# Stromlaufplan_3D-Drucker-Dominik_und_Sam.net
KiCad netlist of a schematic drawn in EAGLE
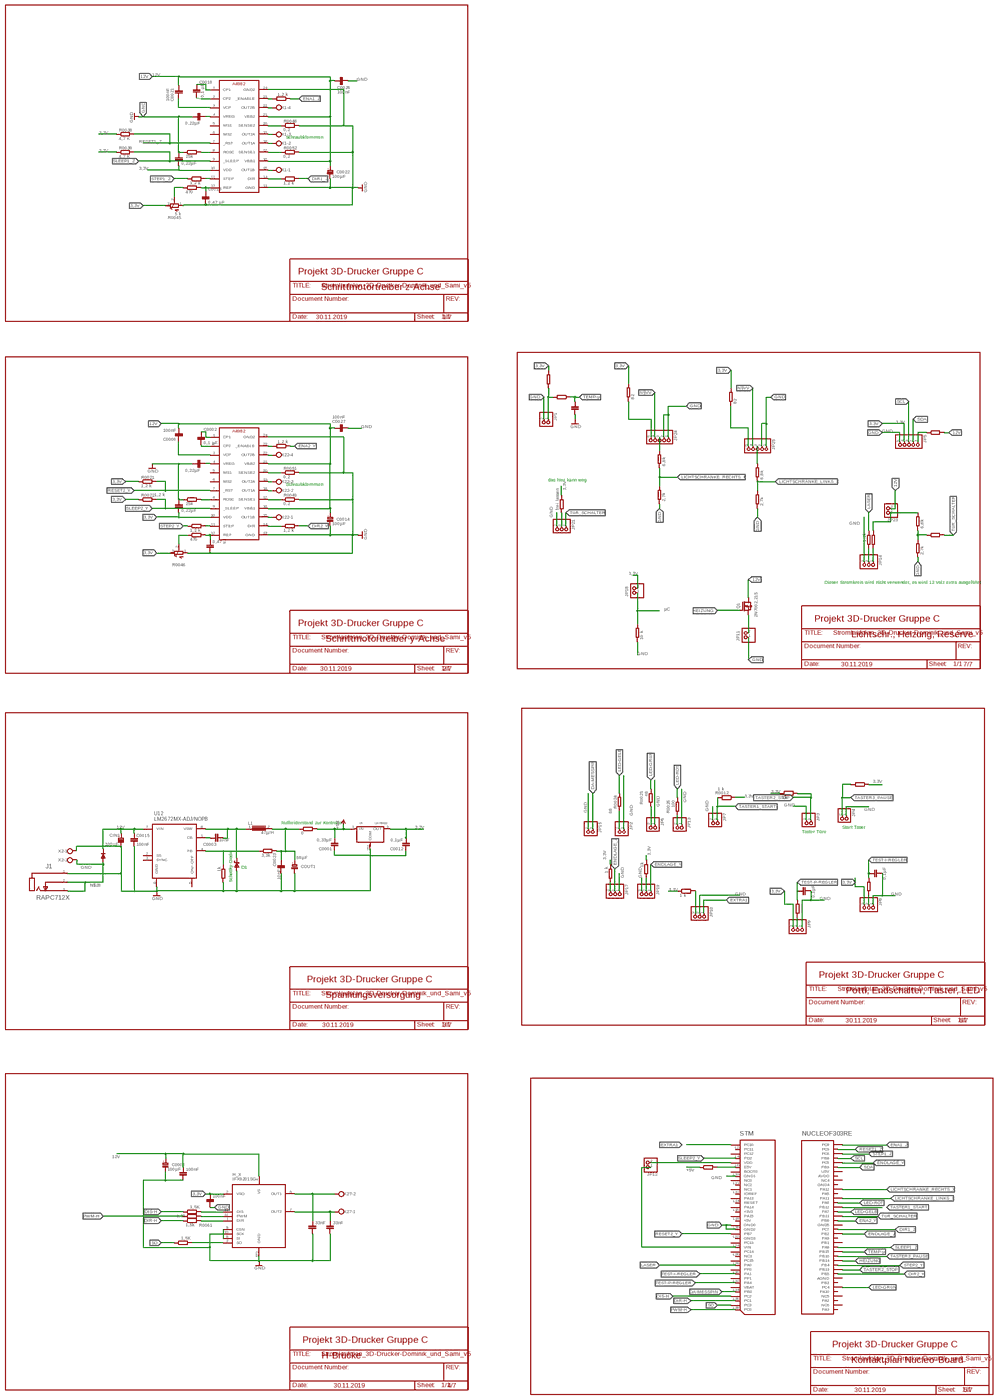
[diagram p0: schematic, sheet 1, overview]
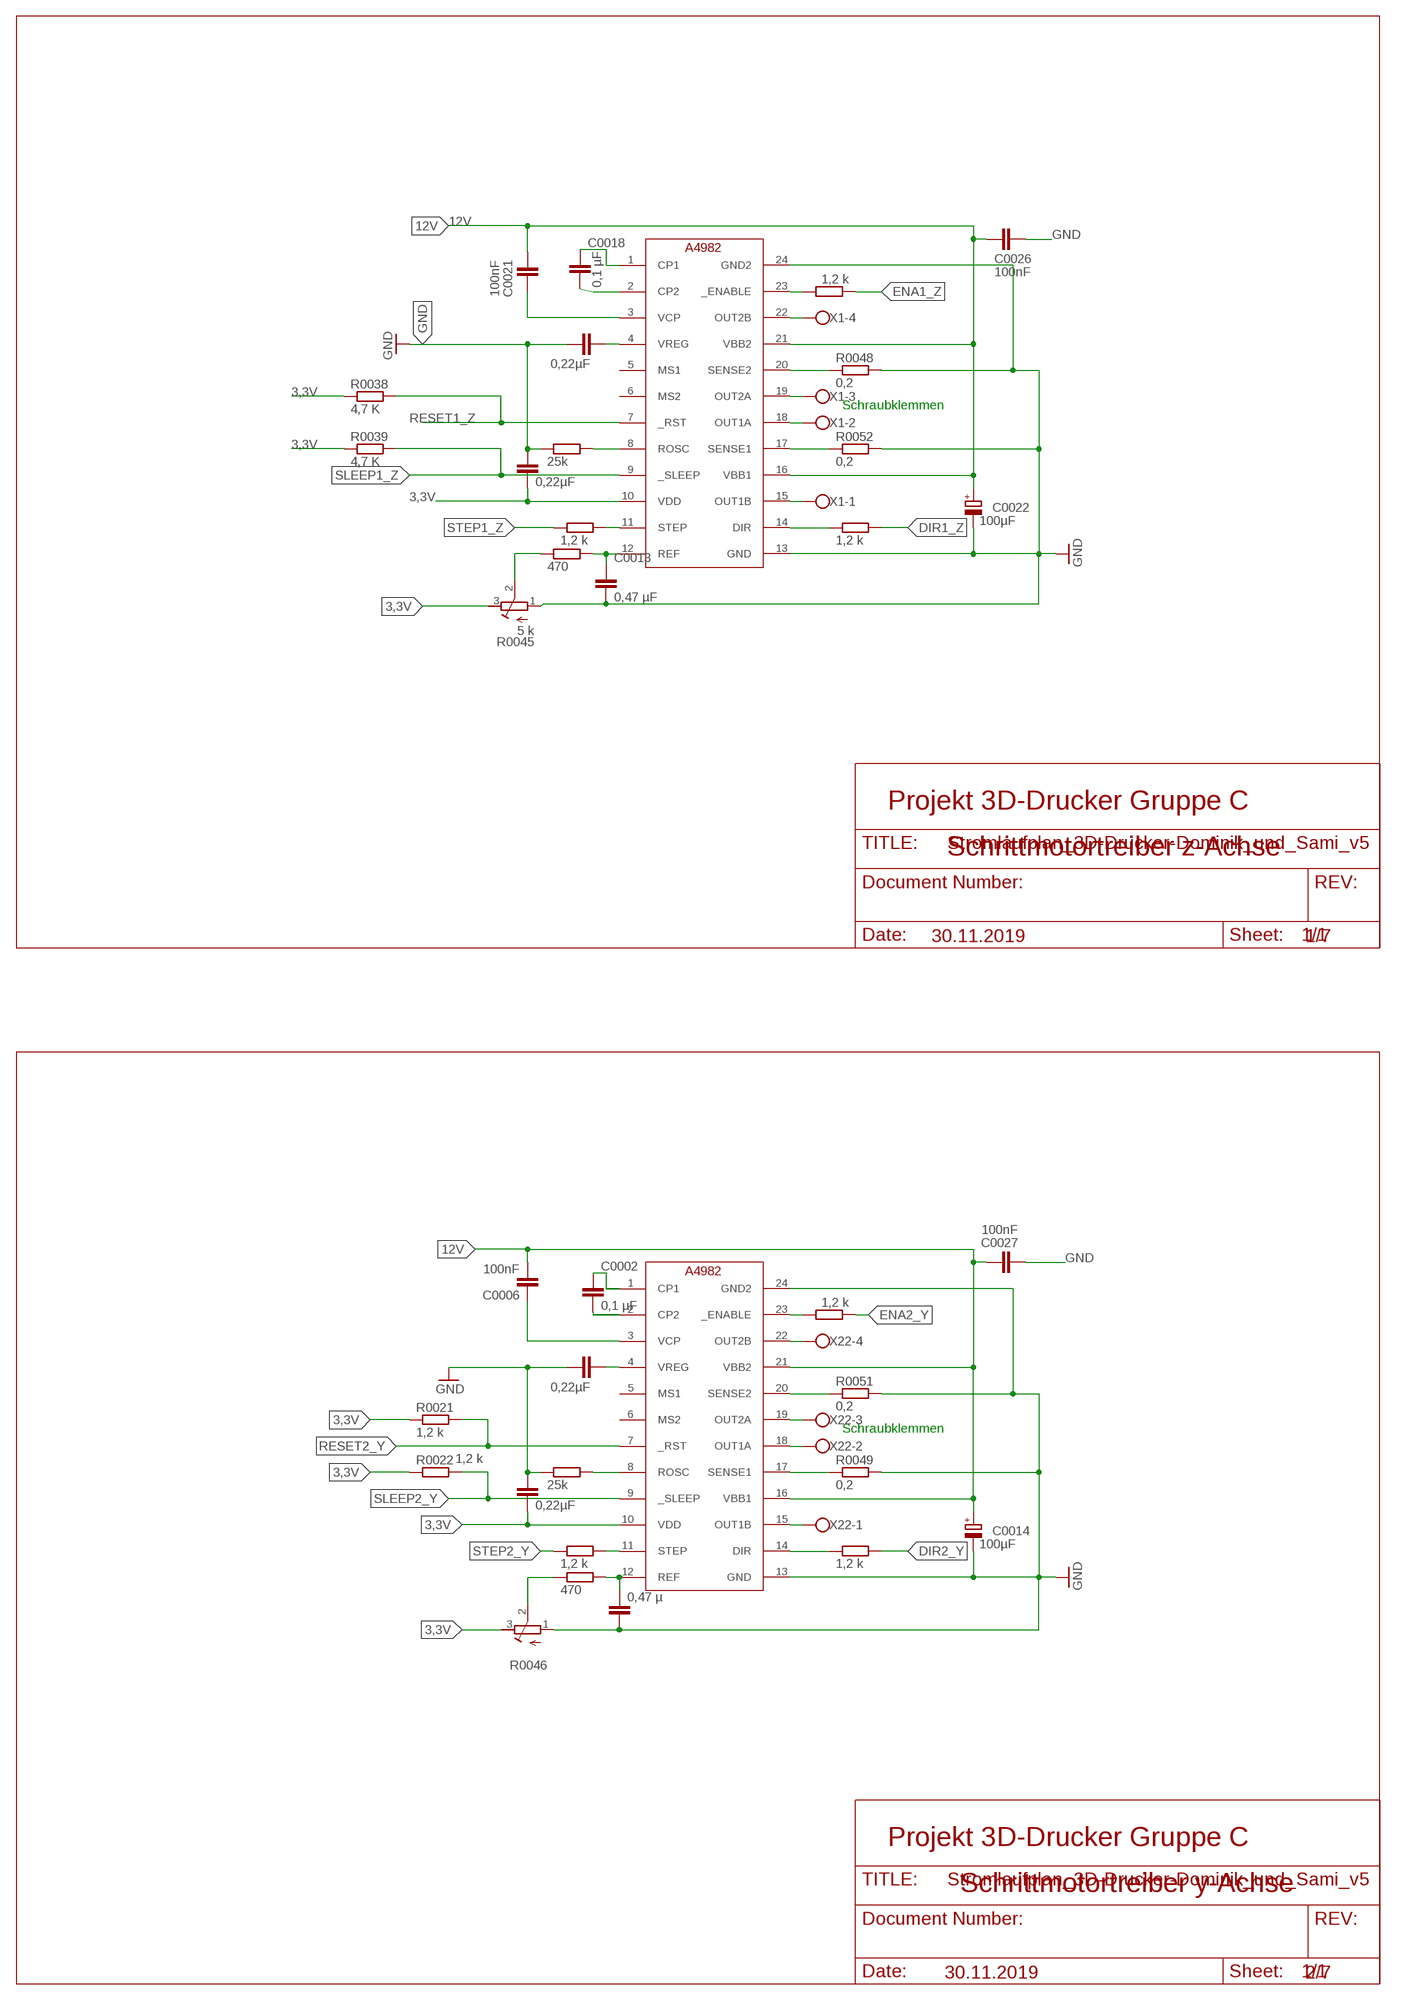
[diagram p1: schematic, sheet 1, part 1 of 4]
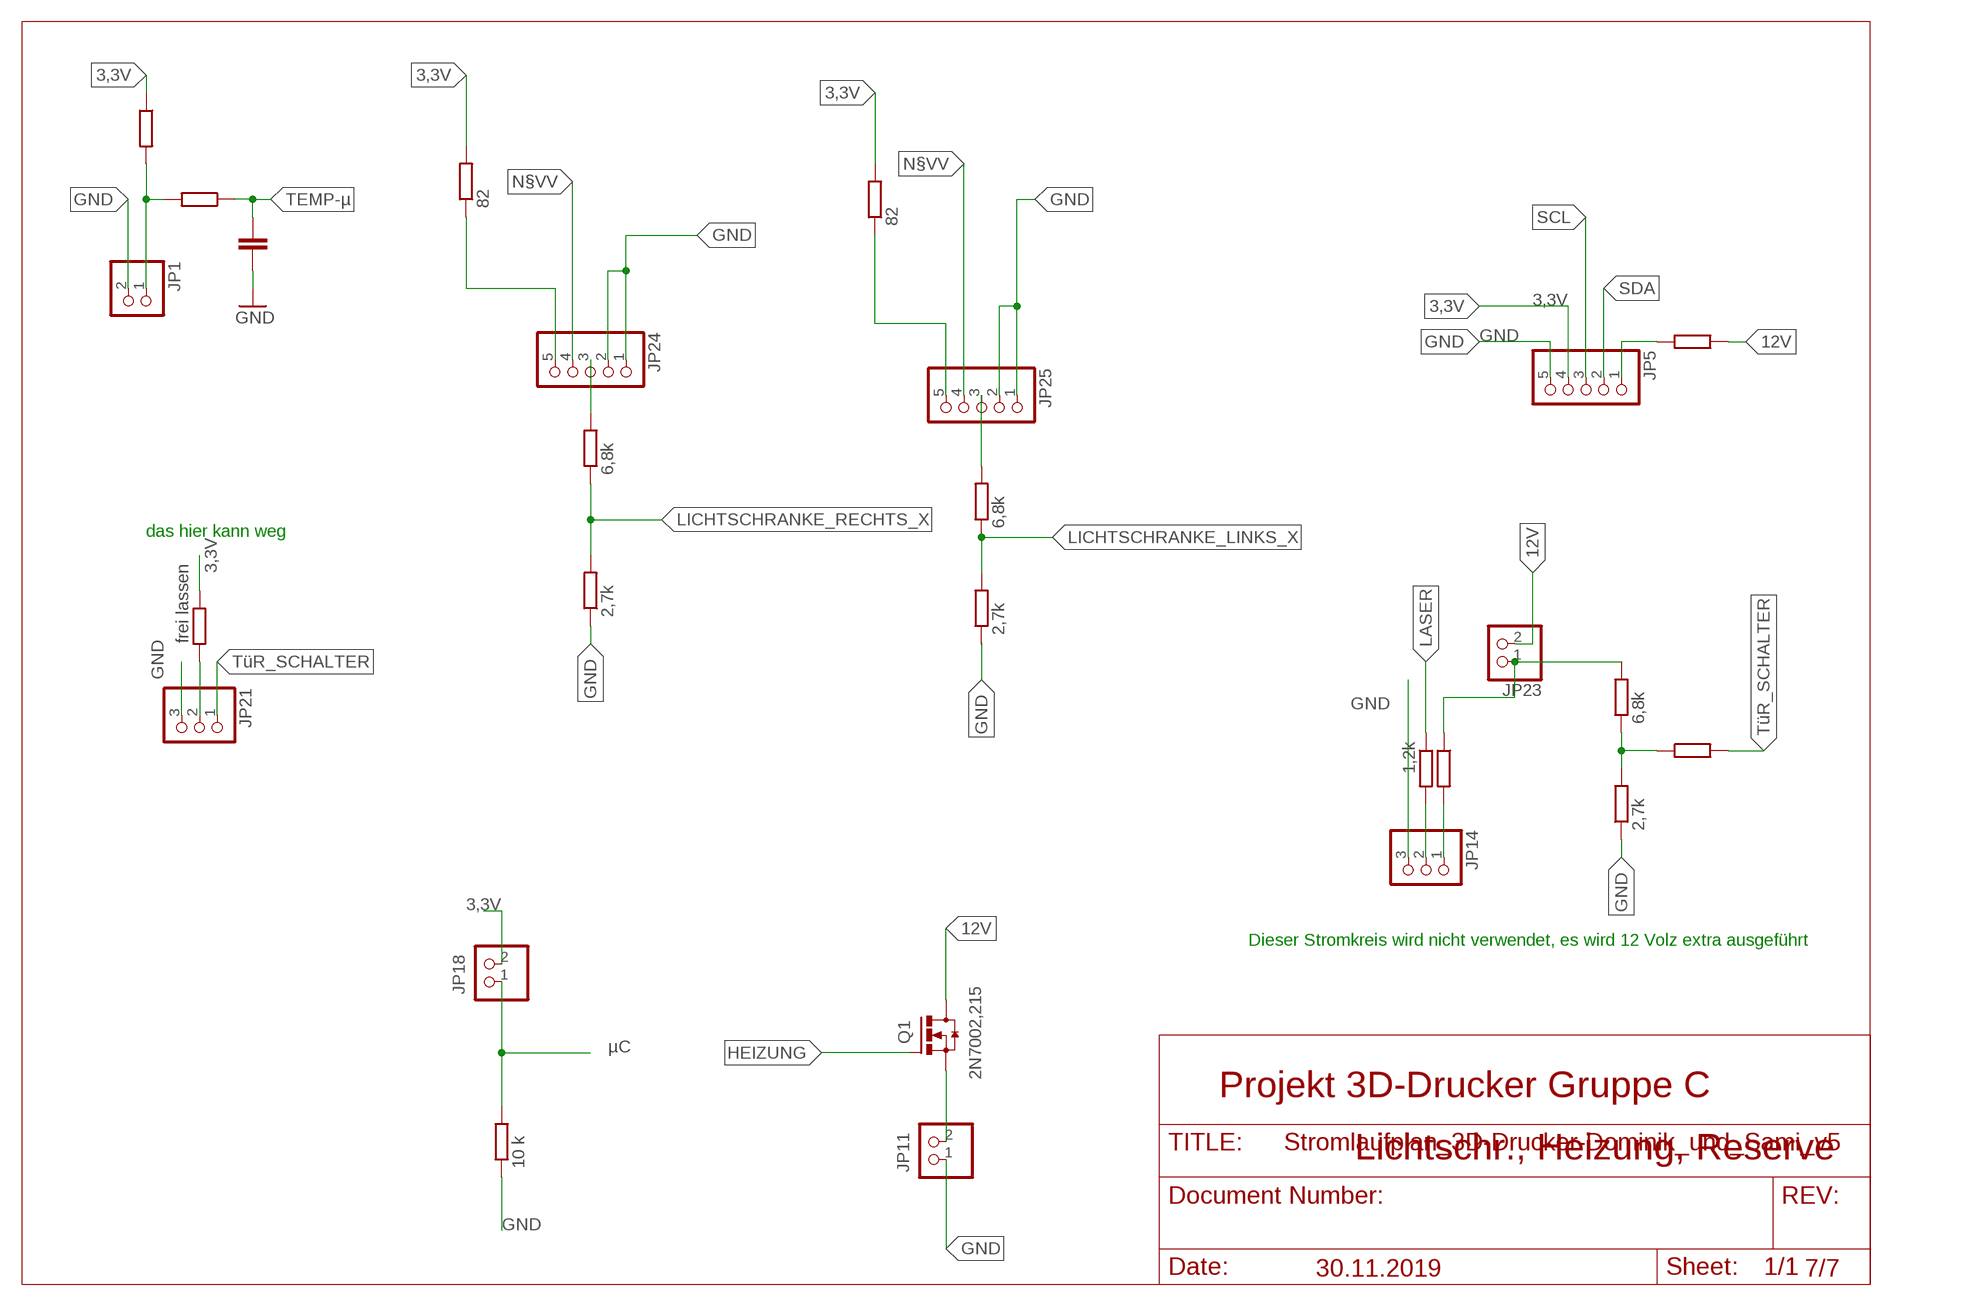
[diagram p2: schematic, sheet 1, part 2 of 4]
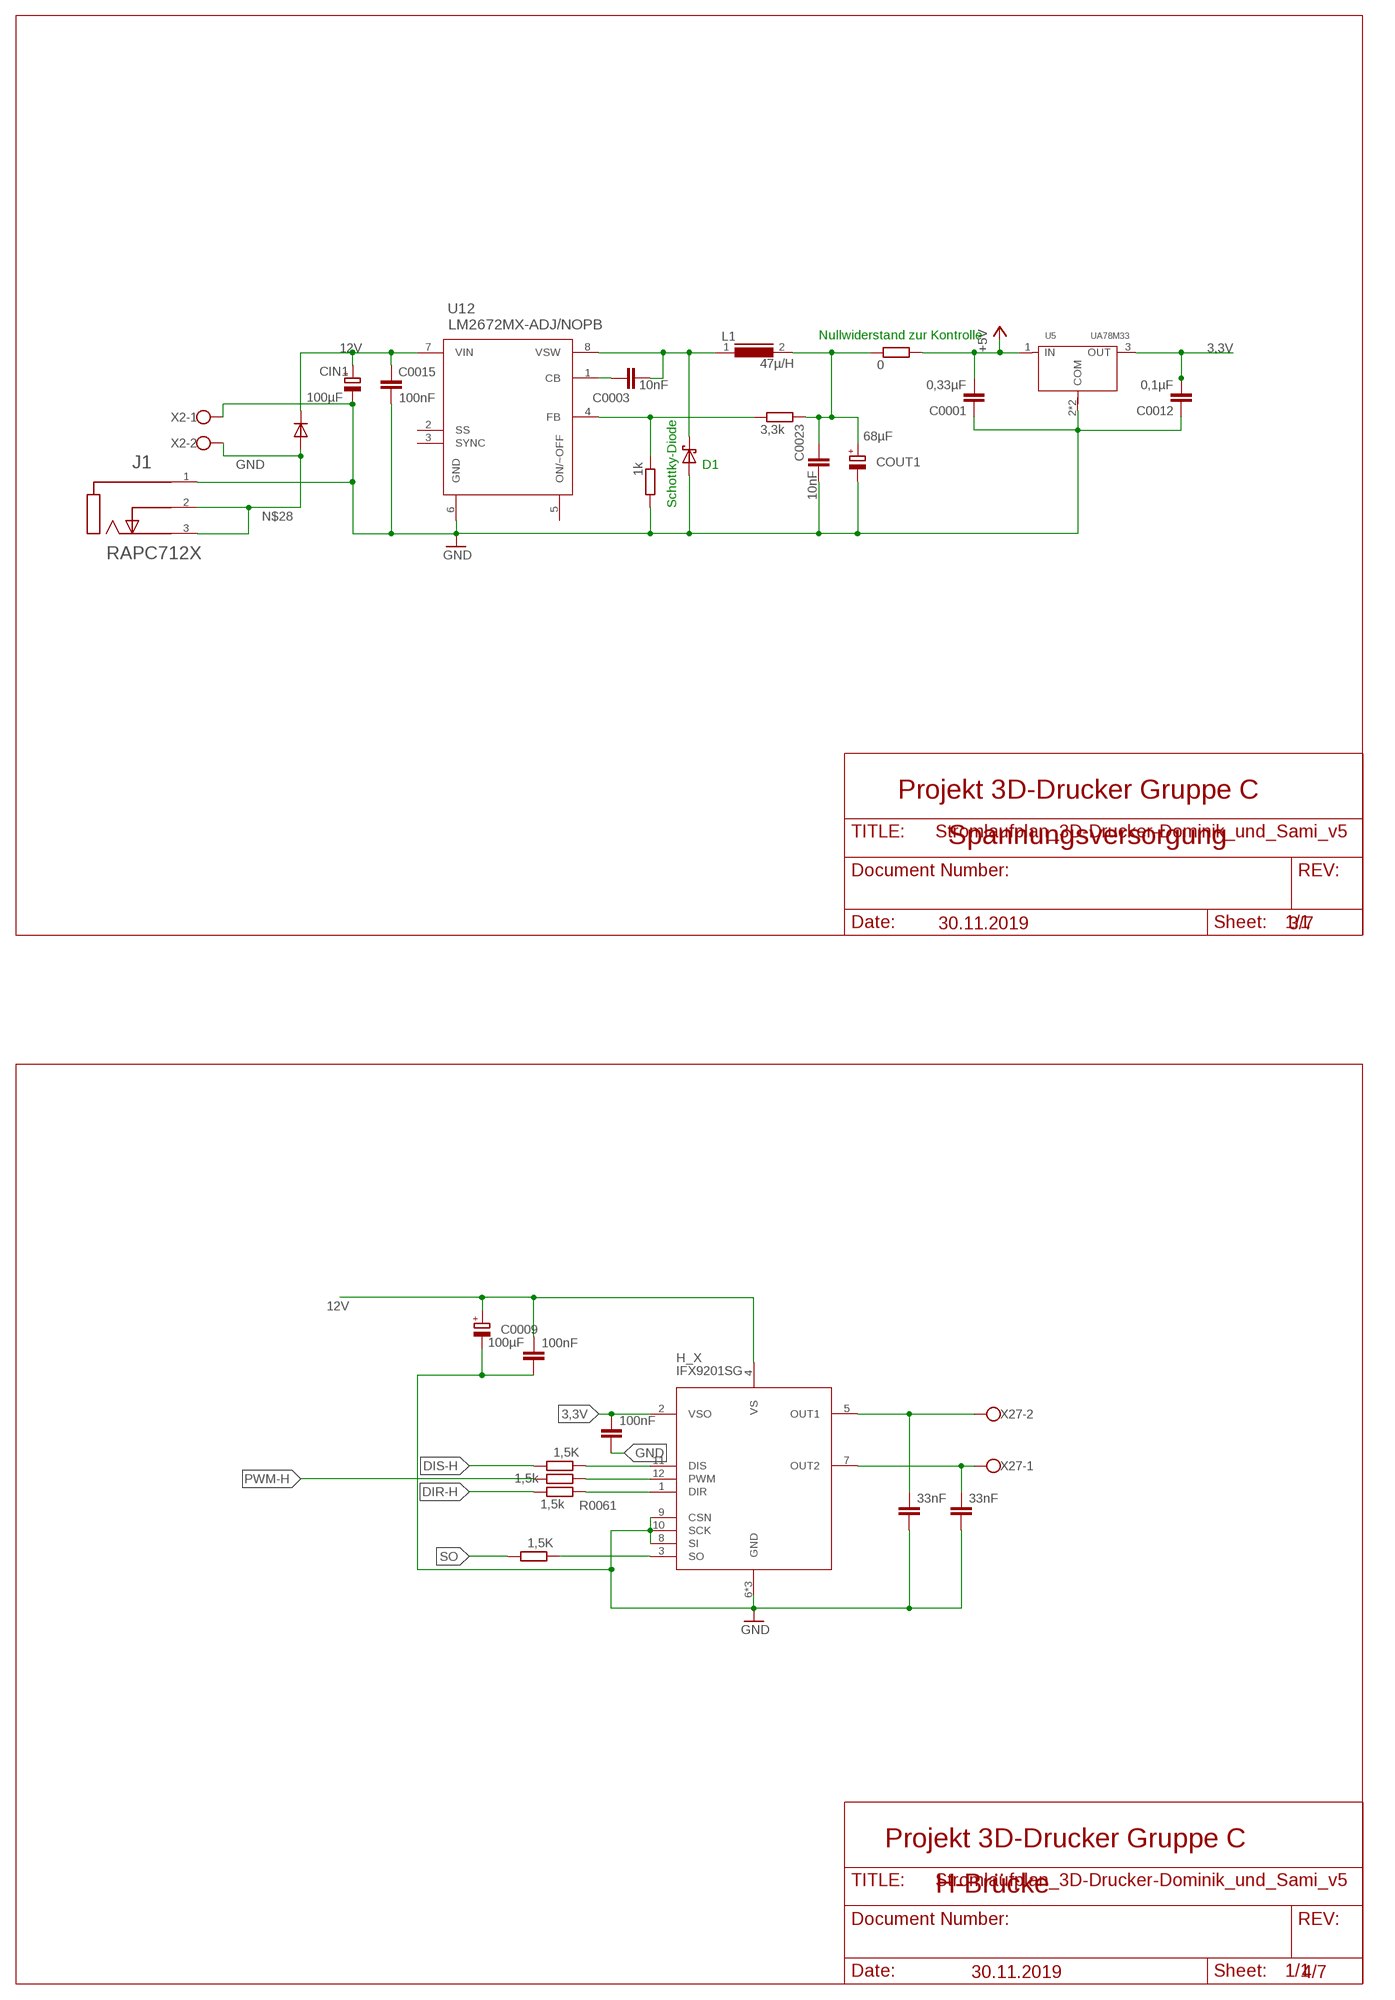
[diagram p3: schematic, sheet 1, part 3 of 4]
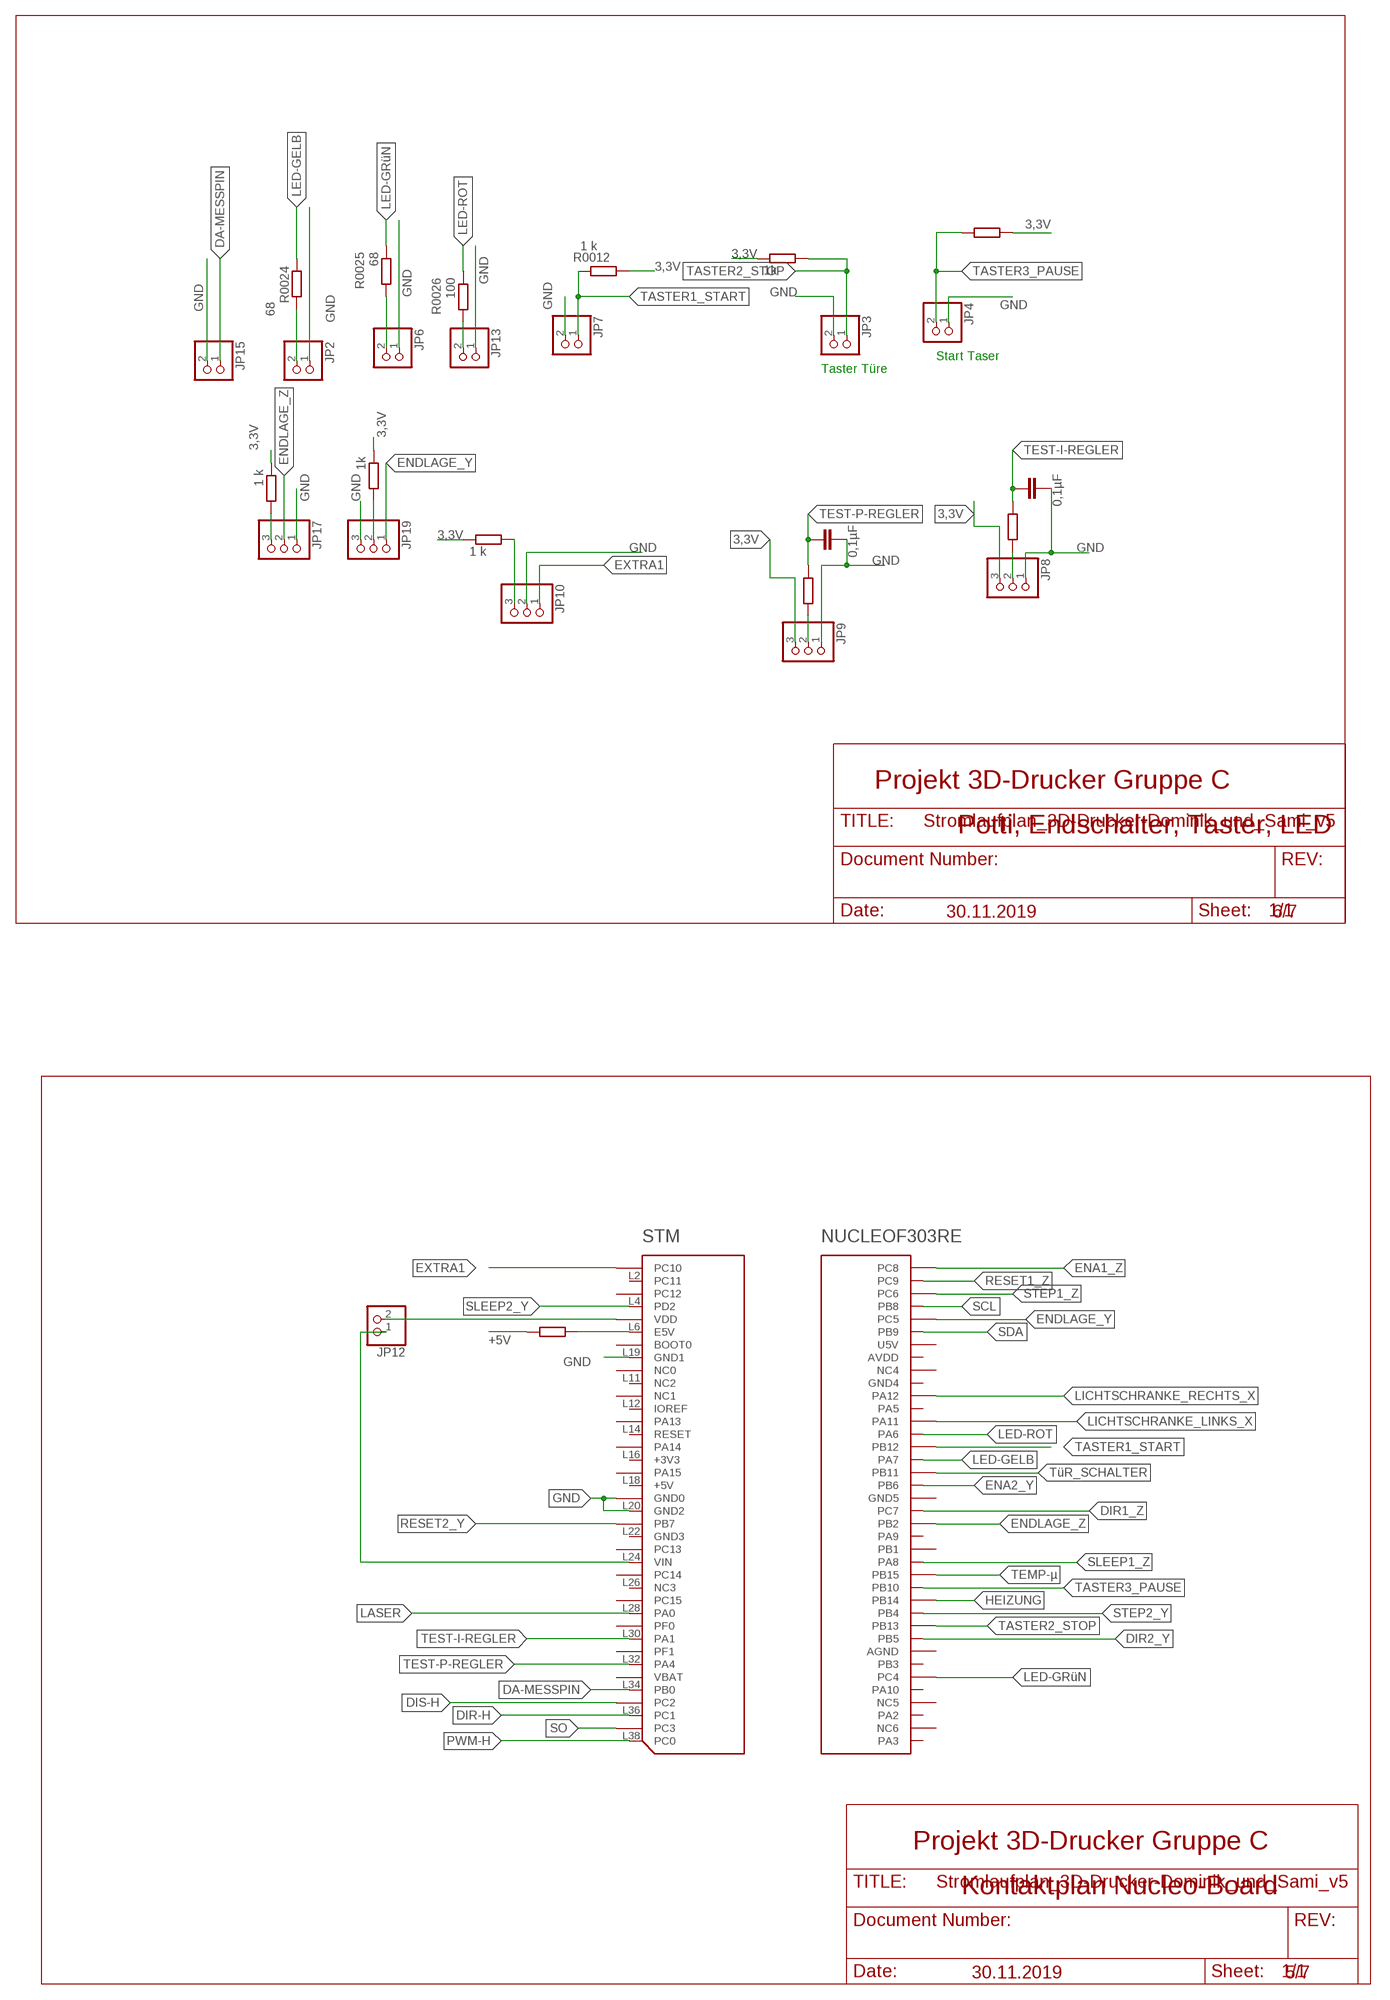
[diagram p4: schematic, sheet 1, part 4 of 4]

(export (version "E")
  (design (tool "Eeschema 10.0.6"))
  (components
    (comp (ref "A4982_Y")
      (value "A4982_STEPDRIVER")
      (footprint "eagle-import:TSSOP24")
      (libsource (lib "eagle-import") (part "A4982_STEPDRIVER"))
    )
    (comp (ref "A4982_Y1")
      (value "A4982_STEPDRIVER")
      (footprint "eagle-import:TSSOP24")
      (libsource (lib "eagle-import") (part "A4982_STEPDRIVER"))
    )
    (comp (ref "C0001")
      (value "0,33µF")
      (footprint "eagle-import:C0603")
      (libsource (lib "eagle-import") (part "C-EUC0603"))
    )
    (comp (ref "C0002")
      (value "0,1 µF")
      (footprint "eagle-import:C0603")
      (libsource (lib "eagle-import") (part "C-EUC0603"))
    )
    (comp (ref "C0003")
      (value "10nF")
      (footprint "eagle-import:C0603")
      (libsource (lib "eagle-import") (part "C-EUC0603"))
    )
    (comp (ref "C0004")
      (value "0,22µF")
      (footprint "eagle-import:C0603")
      (libsource (lib "eagle-import") (part "C-EUC0603"))
    )
    (comp (ref "C0005")
      (value "0,22µF")
      (footprint "eagle-import:C0603")
      (libsource (lib "eagle-import") (part "C-EUC0603"))
    )
    (comp (ref "C0006")
      (value "100nF")
      (footprint "eagle-import:C0603")
      (libsource (lib "eagle-import") (part "C-EUC0603"))
    )
    (comp (ref "C0007")
      (value "33nF")
      (footprint "eagle-import:C0805")
      (libsource (lib "eagle-import") (part "C-EUC0805"))
    )
    (comp (ref "C0008")
      (value "33nF")
      (footprint "eagle-import:C0805")
      (libsource (lib "eagle-import") (part "C-EUC0805"))
    )
    (comp (ref "C0009")
      (value "100µF")
      (footprint "eagle-import:UD-8X10_NICHICON")
      (libsource (lib "eagle-import") (part "CPOL-EUUD-8X10"))
    )
    (comp (ref "C0010")
      (value "0,47 µ")
      (footprint "eagle-import:C0805")
      (libsource (lib "eagle-import") (part "C-EUC0805"))
    )
    (comp (ref "C0011")
      (value "C-EUC0805")
      (footprint "eagle-import:C0805")
      (libsource (lib "eagle-import") (part "C-EUC0805"))
    )
    (comp (ref "C0012")
      (value "0,1µF")
      (footprint "eagle-import:C0603")
      (libsource (lib "eagle-import") (part "C-EUC0603"))
    )
    (comp (ref "C0013")
      (value "0,47 µF")
      (footprint "eagle-import:C0603")
      (libsource (lib "eagle-import") (part "C-EUC0603"))
    )
    (comp (ref "C0014")
      (value "100µF")
      (footprint "eagle-import:UD-8X10_NICHICON")
      (libsource (lib "eagle-import") (part "CPOL-EUUD-8X10"))
    )
    (comp (ref "C0015")
      (value "100nF")
      (footprint "eagle-import:C0603")
      (libsource (lib "eagle-import") (part "C-EUC0603"))
    )
    (comp (ref "C0016")
      (value "100nF")
      (footprint "eagle-import:C0805")
      (libsource (lib "eagle-import") (part "C-EUC0805"))
    )
    (comp (ref "C0018")
      (value "0,1 µF")
      (footprint "eagle-import:C0603")
      (libsource (lib "eagle-import") (part "C-EUC0603"))
    )
    (comp (ref "C0019")
      (value "0,22µF")
      (footprint "eagle-import:C0603")
      (libsource (lib "eagle-import") (part "C-EUC0603"))
    )
    (comp (ref "C0020")
      (value "0,22µF")
      (footprint "eagle-import:C0603")
      (libsource (lib "eagle-import") (part "C-EUC0603"))
    )
    (comp (ref "C0021")
      (value "100nF")
      (footprint "eagle-import:C0603")
      (libsource (lib "eagle-import") (part "C-EUC0603"))
    )
    (comp (ref "C0022")
      (value "100µF")
      (footprint "eagle-import:UD-8X10_NICHICON")
      (libsource (lib "eagle-import") (part "CPOL-EUUD-8X10"))
    )
    (comp (ref "C0023")
      (value "10nF")
      (footprint "eagle-import:C0603")
      (libsource (lib "eagle-import") (part "C-EUC0603"))
    )
    (comp (ref "C0024")
      (value "0,1µF")
      (footprint "eagle-import:C0603")
      (libsource (lib "eagle-import") (part "C-EUC0603"))
    )
    (comp (ref "C0025")
      (value "0,1µF")
      (footprint "eagle-import:C0603")
      (libsource (lib "eagle-import") (part "C-EUC0603"))
    )
    (comp (ref "C0026")
      (value "100nF")
      (footprint "eagle-import:C0603")
      (libsource (lib "eagle-import") (part "C-EUC0603"))
    )
    (comp (ref "C0027")
      (value "100nF")
      (footprint "eagle-import:C0603")
      (libsource (lib "eagle-import") (part "C-EUC0603"))
    )
    (comp (ref "C0041")
      (value "100nF")
      (footprint "eagle-import:C0805")
      (libsource (lib "eagle-import") (part "C-EUC0805"))
    )
    (comp (ref "CIN1")
      (value "100µF")
      (footprint "eagle-import:140CLH-1010")
      (libsource (lib "eagle-import") (part "CPOL-EU140CLH-1010"))
    )
    (comp (ref "COUT1")
      (value "68µF")
      (footprint "eagle-import:140CLH-1010")
      (libsource (lib "eagle-import") (part "CPOL-EU140CLH-1010"))
    )
    (comp (ref "D1")
      (value "1N5819HW-7-F")
      (footprint "eagle-import:SOD-123_MINI-SMA")
      (libsource (lib "eagle-import") (part "1N5819HW-7-F"))
    )
    (comp (ref "D12")
      (value "MURS360BT3G")
      (footprint "eagle-import:SMB")
      (libsource (lib "eagle-import") (part "MURS360BT3G"))
    )
    (comp (ref "H_X")
      (value "IFX9201SG")
      (footprint "eagle-import:BSOP-12")
      (libsource (lib "eagle-import") (part "IFX9201SG"))
    )
    (comp (ref "J1")
      (value "RAPC712X")
      (footprint "eagle-import:SWC_RAPC712X")
      (fields (field (name "MF") "Switchcraft"))
      (libsource (lib "eagle-import") (part "RAPC712X"))
    )
    (comp (ref "JP1")
      (value "PINHD-1X2")
      (footprint "eagle-import:1X02")
      (libsource (lib "eagle-import") (part "PINHD-1X2"))
    )
    (comp (ref "JP2")
      (value "PINHD-1X2")
      (footprint "eagle-import:1X02")
      (libsource (lib "eagle-import") (part "PINHD-1X2"))
    )
    (comp (ref "JP3")
      (value "PINHD-1X2")
      (footprint "eagle-import:1X02")
      (libsource (lib "eagle-import") (part "PINHD-1X2"))
    )
    (comp (ref "JP4")
      (value "PINHD-1X2")
      (footprint "eagle-import:1X02")
      (libsource (lib "eagle-import") (part "PINHD-1X2"))
    )
    (comp (ref "JP5")
      (value "PINHD-1X5")
      (footprint "eagle-import:1X05")
      (libsource (lib "eagle-import") (part "PINHD-1X5"))
    )
    (comp (ref "JP6")
      (value "PINHD-1X2")
      (footprint "eagle-import:1X02")
      (libsource (lib "eagle-import") (part "PINHD-1X2"))
    )
    (comp (ref "JP7")
      (value "PINHD-1X2")
      (footprint "eagle-import:1X02")
      (libsource (lib "eagle-import") (part "PINHD-1X2"))
    )
    (comp (ref "JP8")
      (value "PINHD-1X3")
      (footprint "eagle-import:1X03")
      (libsource (lib "eagle-import") (part "PINHD-1X3"))
    )
    (comp (ref "JP9")
      (value "PINHD-1X3")
      (footprint "eagle-import:1X03")
      (libsource (lib "eagle-import") (part "PINHD-1X3"))
    )
    (comp (ref "JP10")
      (value "PINHD-1X3")
      (footprint "eagle-import:1X03")
      (libsource (lib "eagle-import") (part "PINHD-1X3"))
    )
    (comp (ref "JP11")
      (value "PINHD-1X2")
      (footprint "eagle-import:1X02")
      (libsource (lib "eagle-import") (part "PINHD-1X2"))
    )
    (comp (ref "JP12")
      (value "PINHD-1X2")
      (footprint "eagle-import:1X02")
      (libsource (lib "eagle-import") (part "PINHD-1X2"))
    )
    (comp (ref "JP13")
      (value "PINHD-1X2")
      (footprint "eagle-import:1X02")
      (libsource (lib "eagle-import") (part "PINHD-1X2"))
    )
    (comp (ref "JP14")
      (value "PINHD-1X3")
      (footprint "eagle-import:1X03")
      (libsource (lib "eagle-import") (part "PINHD-1X3"))
    )
    (comp (ref "JP15")
      (value "PINHD-1X2")
      (footprint "eagle-import:1X02")
      (libsource (lib "eagle-import") (part "PINHD-1X2"))
    )
    (comp (ref "JP17")
      (value "PINHD-1X3")
      (footprint "eagle-import:1X03")
      (libsource (lib "eagle-import") (part "PINHD-1X3"))
    )
    (comp (ref "JP18")
      (value "PINHD-1X2")
      (footprint "eagle-import:1X02")
      (libsource (lib "eagle-import") (part "PINHD-1X2"))
    )
    (comp (ref "JP19")
      (value "PINHD-1X3")
      (footprint "eagle-import:1X03")
      (libsource (lib "eagle-import") (part "PINHD-1X3"))
    )
    (comp (ref "JP21")
      (value "PINHD-1X3")
      (footprint "eagle-import:1X03")
      (libsource (lib "eagle-import") (part "PINHD-1X3"))
    )
    (comp (ref "JP23")
      (value "PINHD-1X2")
      (footprint "eagle-import:1X02")
      (libsource (lib "eagle-import") (part "PINHD-1X2"))
    )
    (comp (ref "JP24")
      (value "PINHD-1X5")
      (footprint "eagle-import:1X05")
      (libsource (lib "eagle-import") (part "PINHD-1X5"))
    )
    (comp (ref "JP25")
      (value "PINHD-1X5")
      (footprint "eagle-import:1X05")
      (libsource (lib "eagle-import") (part "PINHD-1X5"))
    )
    (comp (ref "L1")
      (value "47µ/H")
      (footprint "eagle-import:INDUCTOR")
      (libsource (lib "eagle-import") (part "SRR1240-680M"))
    )
    (comp (ref "Q1")
      (value "2N7002,215")
      (footprint "eagle-import:SOT23-3")
      (fields
        (field (name "DIGIKEY_PART_NUMBER") "1727-2764-1-ND")
        (field (name "MANUFACTURER") "Nexperia USA Inc.")
        (field (name "CREATED_BY") "PCBLayout.com")
      )
      (libsource (lib "eagle-import") (part "2N7002,215"))
    )
    (comp (ref "R0001")
      (value "1,5K")
      (footprint "eagle-import:R0603")
      (libsource (lib "eagle-import") (part "R-EU_R0603"))
    )
    (comp (ref "R0002")
      (value "6,8k")
      (footprint "eagle-import:R0603")
      (libsource (lib "eagle-import") (part "R-EU_R0603"))
    )
    (comp (ref "R0003")
      (value "1k")
      (footprint "eagle-import:R0603")
      (libsource (lib "eagle-import") (part "R-EU_R0603"))
    )
    (comp (ref "R0004")
      (value "2,7k")
      (footprint "eagle-import:R0603")
      (libsource (lib "eagle-import") (part "R-EU_R0603"))
    )
    (comp (ref "R0005")
      (value "6,8k")
      (footprint "eagle-import:R0603")
      (libsource (lib "eagle-import") (part "R-EU_R0603"))
    )
    (comp (ref "R0006")
      (value "25k")
      (footprint "eagle-import:R0603")
      (libsource (lib "eagle-import") (part "R-EU_R0603"))
    )
    (comp (ref "R0007")
      (value "10 k")
      (footprint "eagle-import:R0603")
      (libsource (lib "eagle-import") (part "R-EU_R0603"))
    )
    (comp (ref "R0008")
      (value "R-EU_R0603")
      (footprint "eagle-import:R0603")
      (libsource (lib "eagle-import") (part "R-EU_R0603"))
    )
    (comp (ref "R0009")
      (value "1,2 k")
      (footprint "eagle-import:R0603")
      (libsource (lib "eagle-import") (part "R-EU_R0603"))
    )
    (comp (ref "R0010")
      (value "1,2 k")
      (footprint "eagle-import:R0603")
      (libsource (lib "eagle-import") (part "R-EU_R0603"))
    )
    (comp (ref "R0011")
      (value "1,2 k")
      (footprint "eagle-import:R0603")
      (libsource (lib "eagle-import") (part "R-EU_R0603"))
    )
    (comp (ref "R0012")
      (value "1 k")
      (footprint "eagle-import:R0603")
      (libsource (lib "eagle-import") (part "R-EU_R0603"))
    )
    (comp (ref "R0013")
      (value "1k")
      (footprint "eagle-import:R0603")
      (libsource (lib "eagle-import") (part "R-EU_R0603"))
    )
    (comp (ref "R0014")
      (value "R-EU_R0603")
      (footprint "eagle-import:R0603")
      (libsource (lib "eagle-import") (part "R-EU_R0603"))
    )
    (comp (ref "R0015")
      (value "1 k")
      (footprint "eagle-import:R0603")
      (libsource (lib "eagle-import") (part "R-EU_R0603"))
    )
    (comp (ref "R0016")
      (value "R-EU_R0603")
      (footprint "eagle-import:R0603")
      (libsource (lib "eagle-import") (part "R-EU_R0603"))
    )
    (comp (ref "R0017")
      (value "R-EU_R0603")
      (footprint "eagle-import:R0603")
      (libsource (lib "eagle-import") (part "R-EU_R0603"))
    )
    (comp (ref "R0018")
      (value "frei lassen")
      (footprint "eagle-import:R0603")
      (libsource (lib "eagle-import") (part "R-EU_R0603"))
    )
    (comp (ref "R0019")
      (value "25k")
      (footprint "eagle-import:R0603")
      (libsource (lib "eagle-import") (part "R-EU_R0603"))
    )
    (comp (ref "R0020")
      (value "R-EU_R0603")
      (footprint "eagle-import:R0603")
      (libsource (lib "eagle-import") (part "R-EU_R0603"))
    )
    (comp (ref "R0021")
      (value "1,2 k")
      (footprint "eagle-import:R0603")
      (libsource (lib "eagle-import") (part "R-EU_R0603"))
    )
    (comp (ref "R0022")
      (value "1,2 k")
      (footprint "eagle-import:R0603")
      (libsource (lib "eagle-import") (part "R-EU_R0603"))
    )
    (comp (ref "R0023")
      (value "470")
      (footprint "eagle-import:R0603")
      (libsource (lib "eagle-import") (part "R-EU_R0603"))
    )
    (comp (ref "R0024")
      (value "68")
      (footprint "eagle-import:R0603")
      (libsource (lib "eagle-import") (part "R-EU_R0603"))
    )
    (comp (ref "R0025")
      (value "68")
      (footprint "eagle-import:R0603")
      (libsource (lib "eagle-import") (part "R-EU_R0603"))
    )
    (comp (ref "R0026")
      (value "100")
      (footprint "eagle-import:R0603")
      (libsource (lib "eagle-import") (part "R-EU_R0603"))
    )
    (comp (ref "R0027")
      (value "R-EU_R0603")
      (footprint "eagle-import:R0603")
      (libsource (lib "eagle-import") (part "R-EU_R0603"))
    )
    (comp (ref "R0028")
      (value "2,7k")
      (footprint "eagle-import:R0603")
      (libsource (lib "eagle-import") (part "R-EU_R0603"))
    )
    (comp (ref "R0029")
      (value "82")
      (footprint "eagle-import:R0603")
      (libsource (lib "eagle-import") (part "R-EU_R0603"))
    )
    (comp (ref "R0030")
      (value "R-EU_R0603")
      (footprint "eagle-import:R0603")
      (libsource (lib "eagle-import") (part "R-EU_R0603"))
    )
    (comp (ref "R0031")
      (value "R-EU_R0603")
      (footprint "eagle-import:R0603")
      (libsource (lib "eagle-import") (part "R-EU_R0603"))
    )
    (comp (ref "R0032")
      (value "82")
      (footprint "eagle-import:R0603")
      (libsource (lib "eagle-import") (part "R-EU_R0603"))
    )
    (comp (ref "R0033")
      (value "1 k")
      (footprint "eagle-import:R0603")
      (libsource (lib "eagle-import") (part "R-EU_R0603"))
    )
    (comp (ref "R0034")
      (value "1,2 k")
      (footprint "eagle-import:R0603")
      (libsource (lib "eagle-import") (part "R-EU_R0603"))
    )
    (comp (ref "R0035")
      (value "1,2 k")
      (footprint "eagle-import:R0603")
      (libsource (lib "eagle-import") (part "R-EU_R0603"))
    )
    (comp (ref "R0036")
      (value "1,2 k")
      (footprint "eagle-import:R0603")
      (libsource (lib "eagle-import") (part "R-EU_R0603"))
    )
    (comp (ref "R0037")
      (value "470")
      (footprint "eagle-import:R0603")
      (libsource (lib "eagle-import") (part "R-EU_R0603"))
    )
    (comp (ref "R0038")
      (value "4,7 K")
      (footprint "eagle-import:R0603")
      (libsource (lib "eagle-import") (part "R-EU_R0603"))
    )
    (comp (ref "R0039")
      (value "4,7 K")
      (footprint "eagle-import:R0603")
      (libsource (lib "eagle-import") (part "R-EU_R0603"))
    )
    (comp (ref "R0042")
      (value "1,2k")
      (footprint "eagle-import:R0603")
      (libsource (lib "eagle-import") (part "R-EU_R0603"))
    )
    (comp (ref "R0043")
      (value "6,8k")
      (footprint "eagle-import:R0603")
      (libsource (lib "eagle-import") (part "R-EU_R0603"))
    )
    (comp (ref "R0044")
      (value "2,7k")
      (footprint "eagle-import:R0603")
      (libsource (lib "eagle-import") (part "R-EU_R0603"))
    )
    (comp (ref "R0045")
      (value "5 k")
      (footprint "eagle-import:RTRIM3296Y")
      (libsource (lib "eagle-import") (part "R-TRIMM3296Y"))
    )
    (comp (ref "R0046")
      (value "R-TRIMM3296Y")
      (footprint "eagle-import:RTRIM3296Y")
      (libsource (lib "eagle-import") (part "R-TRIMM3296Y"))
    )
    (comp (ref "R0048")
      (value "0,2")
      (footprint "eagle-import:R2512")
      (libsource (lib "eagle-import") (part "rcl_334_R-EU_R2512"))
    )
    (comp (ref "R0049")
      (value "0,2")
      (footprint "eagle-import:R2512")
      (libsource (lib "eagle-import") (part "rcl_334_R-EU_R2512"))
    )
    (comp (ref "R0051")
      (value "0,2")
      (footprint "eagle-import:R2512")
      (libsource (lib "eagle-import") (part "rcl_334_R-EU_R2512"))
    )
    (comp (ref "R0052")
      (value "0,2")
      (footprint "eagle-import:R2512")
      (libsource (lib "eagle-import") (part "rcl_334_R-EU_R2512"))
    )
    (comp (ref "R0053")
      (value "R-EU_R0603")
      (footprint "eagle-import:R0603")
      (libsource (lib "eagle-import") (part "R-EU_R0603"))
    )
    (comp (ref "R0061")
      (value "1,5k")
      (footprint "eagle-import:R0603")
      (libsource (lib "eagle-import") (part "R-EU_R0603"))
    )
    (comp (ref "R0062")
      (value "1,5k")
      (footprint "eagle-import:R0603")
      (libsource (lib "eagle-import") (part "R-EU_R0603"))
    )
    (comp (ref "R0063")
      (value "1,5K")
      (footprint "eagle-import:R0603")
      (libsource (lib "eagle-import") (part "R-EU_R0603"))
    )
    (comp (ref "STM")
      (value "NUCLEOF303RE")
      (footprint "eagle-import:DIL40")
      (libsource (lib "eagle-import") (part "NUCLEOF303RE"))
    )
    (comp (ref "TEST_R")
      (value "0")
      (footprint "eagle-import:R0603")
      (libsource (lib "eagle-import") (part "R-EU_R0603"))
    )
    (comp (ref "TEST_R2")
      (value "3,3k")
      (footprint "eagle-import:R0603")
      (libsource (lib "eagle-import") (part "R-EU_R0603"))
    )
    (comp (ref "TEST_R3")
      (value "1k")
      (footprint "eagle-import:R0603")
      (libsource (lib "eagle-import") (part "R-EU_R0603"))
    )
    (comp (ref "U5")
      (value "UA78M33")
      (footprint "eagle-import:SOT-223")
      (fields (field (name "MF") "Texas Instruments") (field (name "MP") "UA78M33CDCYR"))
      (libsource (lib "eagle-import") (part "UA78M33"))
    )
    (comp (ref "U12")
      (value "LM2672MX-ADJ/NOPB")
      (footprint "eagle-import:SOIC-8")
      (fields (field (name "MF") "Texas Instruments"))
      (libsource (lib "eagle-import") (part "LM2672MX-ADJ/NOPB"))
    )
    (comp (ref "X1")
      (value "SCHRAUBKLEMME_4X")
      (footprint "eagle-import:W237-4")
      (libsource (lib "eagle-import") (part "SCHRAUBKLEMME_4X"))
    )
    (comp (ref "X2")
      (value "SCHRAUBKLEMME_2X")
      (footprint "eagle-import:W237-102")
      (fields (field (name "MPN") "237-102"))
      (libsource (lib "eagle-import") (part "SCHRAUBKLEMME_2X"))
    )
    (comp (ref "X22")
      (value "SCHRAUBKLEMME_4X")
      (footprint "eagle-import:W237-4")
      (libsource (lib "eagle-import") (part "SCHRAUBKLEMME_4X"))
    )
    (comp (ref "X27")
      (value "SCHRAUBKLEMME_2X")
      (footprint "eagle-import:W237-102")
      (fields (field (name "MPN") "237-102"))
      (libsource (lib "eagle-import") (part "SCHRAUBKLEMME_2X"))
    )
  )
  (nets
    (net (code "1") (name "+5V") (class "Default")
      (node (ref "C0001") (pin "2") (pinfunction "2_2") (pintype "passive"))
      (node (ref "R0027") (pin "1") (pinfunction "1_1") (pintype "passive"))
      (node (ref "TEST_R") (pin "2") (pinfunction "2_2") (pintype "passive"))
      (node (ref "U5") (pin "1") (pinfunction "IN_1") (pintype "bidirectional"))
    )
    (net (code "2") (name "/N$28") (class "Default")
      (node (ref "D12") (pin "2") (pinfunction "P$1_2") (pintype "bidirectional"))
      (node (ref "J1") (pin "2") (pinfunction "SHUNT_2") (pintype "passive"))
      (node (ref "J1") (pin "3") (pinfunction "SLEEVE_3") (pintype "passive"))
      (node (ref "X2") (pin "2") (pinfunction "KL_2") (pintype "passive"))
    )
    (net (code "3") (name "/µC") (class "Default")
      (node (ref "JP18") (pin "1") (pinfunction "1_1") (pintype "passive"))
      (node (ref "R0007") (pin "2") (pinfunction "2_2") (pintype "passive"))
    )
    (net (code "4") (name "3,3V") (class "Default")
      (node (ref "A4982_Y") (pin "10") (pinfunction "VDD_10") (pintype "bidirectional"))
      (node (ref "A4982_Y1") (pin "10") (pinfunction "VDD_10") (pintype "bidirectional"))
      (node (ref "C0005") (pin "1") (pinfunction "1_1") (pintype "passive"))
      (node (ref "C0012") (pin "2") (pinfunction "2_2") (pintype "passive"))
      (node (ref "C0016") (pin "1") (pinfunction "1_1") (pintype "passive"))
      (node (ref "C0020") (pin "1") (pinfunction "1_1") (pintype "passive"))
      (node (ref "H_X") (pin "2") (pinfunction "VSO_2") (pintype "bidirectional"))
      (node (ref "JP18") (pin "2") (pinfunction "2_2") (pintype "passive"))
      (node (ref "JP5") (pin "4") (pinfunction "4_4") (pintype "passive"))
      (node (ref "JP8") (pin "3") (pinfunction "3_3") (pintype "passive"))
      (node (ref "JP9") (pin "3") (pinfunction "3_3") (pintype "passive"))
      (node (ref "R0003") (pin "1") (pinfunction "1_1") (pintype "passive"))
      (node (ref "R0008") (pin "1") (pinfunction "1_1") (pintype "passive"))
      (node (ref "R0012") (pin "1") (pinfunction "1_1") (pintype "passive"))
      (node (ref "R0013") (pin "1") (pinfunction "1_1") (pintype "passive"))
      (node (ref "R0014") (pin "1") (pinfunction "1_1") (pintype "passive"))
      (node (ref "R0015") (pin "1") (pinfunction "1_1") (pintype "passive"))
      (node (ref "R0018") (pin "1") (pinfunction "1_1") (pintype "passive"))
      (node (ref "R0021") (pin "1") (pinfunction "1_1") (pintype "passive"))
      (node (ref "R0022") (pin "1") (pinfunction "1_1") (pintype "passive"))
      (node (ref "R0029") (pin "2") (pinfunction "2_2") (pintype "passive"))
      (node (ref "R0032") (pin "2") (pinfunction "2_2") (pintype "passive"))
      (node (ref "R0033") (pin "1") (pinfunction "1_1") (pintype "passive"))
      (node (ref "R0038") (pin "1") (pinfunction "1_1") (pintype "passive"))
      (node (ref "R0039") (pin "1") (pinfunction "1_1") (pintype "passive"))
      (node (ref "R0045") (pin "3") (pinfunction "E_3") (pintype "passive"))
      (node (ref "R0046") (pin "3") (pinfunction "E_3") (pintype "passive"))
      (node (ref "U5") (pin "3") (pinfunction "OUT_3") (pintype "bidirectional"))
    )
    (net (code "5") (name "12V") (class "Default")
      (node (ref "A4982_Y") (pin "16") (pinfunction "VBB1_16") (pintype "bidirectional"))
      (node (ref "A4982_Y") (pin "21") (pinfunction "VBB2_21") (pintype "bidirectional"))
      (node (ref "A4982_Y1") (pin "16") (pinfunction "VBB1_16") (pintype "bidirectional"))
      (node (ref "A4982_Y1") (pin "21") (pinfunction "VBB2_21") (pintype "bidirectional"))
      (node (ref "C0006") (pin "2") (pinfunction "2_2") (pintype "passive"))
      (node (ref "C0009") (pin "+") (pinfunction "+_+") (pintype "passive"))
      (node (ref "C0014") (pin "+") (pinfunction "+_+") (pintype "passive"))
      (node (ref "C0015") (pin "2") (pinfunction "2_2") (pintype "passive"))
      (node (ref "C0021") (pin "2") (pinfunction "2_2") (pintype "passive"))
      (node (ref "C0022") (pin "+") (pinfunction "+_+") (pintype "passive"))
      (node (ref "C0026") (pin "2") (pinfunction "2_2") (pintype "passive"))
      (node (ref "C0027") (pin "1") (pinfunction "1_1") (pintype "passive"))
      (node (ref "C0041") (pin "1") (pinfunction "1_1") (pintype "passive"))
      (node (ref "CIN1") (pin "+") (pinfunction "+_+") (pintype "passive"))
      (node (ref "D12") (pin "1") (pinfunction "P$2_1") (pintype "bidirectional"))
      (node (ref "H_X") (pin "4") (pinfunction "VS_4") (pintype "bidirectional"))
      (node (ref "JP14") (pin "1") (pinfunction "1_1") (pintype "passive"))
      (node (ref "JP23") (pin "2") (pinfunction "2_2") (pintype "passive"))
      (node (ref "Q1") (pin "3") (pinfunction "D_3") (pintype "passive"))
      (node (ref "R0016") (pin "2") (pinfunction "2_2") (pintype "passive"))
      (node (ref "R0030") (pin "2") (pinfunction "2_2") (pintype "passive"))
      (node (ref "U12") (pin "7") (pinfunction "VIN_7") (pintype "power_in"))
    )
    (net (code "6") (name "DA-MESSPIN") (class "Default")
      (node (ref "JP15") (pin "1") (pinfunction "1_1") (pintype "passive"))
      (node (ref "STM") (pin "L34") (pinfunction "PB0_L34") (pintype "bidirectional"))
    )
    (net (code "7") (name "DIR-H") (class "Default")
      (node (ref "R0061") (pin "1") (pinfunction "1_1") (pintype "passive"))
      (node (ref "STM") (pin "L36") (pinfunction "PC1_L36") (pintype "bidirectional"))
    )
    (net (code "8") (name "DIR1_Z") (class "Default")
      (node (ref "R0036") (pin "2") (pinfunction "2_2") (pintype "passive"))
      (node (ref "STM") (pin "R19") (pinfunction "PC7_R19") (pintype "bidirectional"))
    )
    (net (code "9") (name "DIR2_Y") (class "Default")
      (node (ref "R0011") (pin "2") (pinfunction "2_2") (pintype "passive"))
      (node (ref "STM") (pin "R29") (pinfunction "PB5_R29") (pintype "bidirectional"))
    )
    (net (code "10") (name "DIS-H") (class "Default")
      (node (ref "R0063") (pin "1") (pinfunction "1_1") (pintype "passive"))
      (node (ref "STM") (pin "L35") (pinfunction "PC2_L35") (pintype "bidirectional"))
    )
    (net (code "11") (name "ENA1_Z") (class "Default")
      (node (ref "R0034") (pin "1") (pinfunction "1_1") (pintype "passive"))
      (node (ref "STM") (pin "R2") (pinfunction "PC8_R2") (pintype "bidirectional"))
    )
    (net (code "12") (name "ENA2_Y") (class "Default")
      (node (ref "R0009") (pin "1") (pinfunction "1_1") (pintype "passive"))
      (node (ref "STM") (pin "R17") (pinfunction "PB6_R17") (pintype "bidirectional"))
    )
    (net (code "13") (name "ENDLAGE_Y") (class "Default")
      (node (ref "JP19") (pin "1") (pinfunction "1_1") (pintype "passive"))
      (node (ref "STM") (pin "R6") (pinfunction "PC5_R6") (pintype "bidirectional"))
    )
    (net (code "14") (name "ENDLAGE_Z") (class "Default")
      (node (ref "JP17") (pin "2") (pinfunction "2_2") (pintype "passive"))
      (node (ref "STM") (pin "R22") (pinfunction "PB2_R22") (pintype "bidirectional"))
    )
    (net (code "15") (name "EXTRA1") (class "Default")
      (node (ref "JP10") (pin "1") (pinfunction "1_1") (pintype "passive"))
      (node (ref "STM") (pin "L1") (pinfunction "PC10_L1") (pintype "bidirectional"))
    )
    (net (code "16") (name "GND") (class "Default")
      (node (ref "A4982_Y") (pin "13") (pinfunction "GND_13") (pintype "bidirectional"))
      (node (ref "A4982_Y") (pin "24") (pinfunction "GND2_24") (pintype "bidirectional"))
      (node (ref "A4982_Y1") (pin "13") (pinfunction "GND_13") (pintype "bidirectional"))
      (node (ref "A4982_Y1") (pin "24") (pinfunction "GND2_24") (pintype "bidirectional"))
      (node (ref "C0001") (pin "1") (pinfunction "1_1") (pintype "passive"))
      (node (ref "C0004") (pin "2") (pinfunction "2_2") (pintype "passive"))
      (node (ref "C0005") (pin "2") (pinfunction "2_2") (pintype "passive"))
      (node (ref "C0007") (pin "2") (pinfunction "2_2") (pintype "passive"))
      (node (ref "C0008") (pin "2") (pinfunction "2_2") (pintype "passive"))
      (node (ref "C0009") (pin "-") (pinfunction "-_-") (pintype "passive"))
      (node (ref "C0010") (pin "2") (pinfunction "2_2") (pintype "passive"))
      (node (ref "C0011") (pin "2") (pinfunction "2_2") (pintype "passive"))
      (node (ref "C0012") (pin "1") (pinfunction "1_1") (pintype "passive"))
      (node (ref "C0013") (pin "2") (pinfunction "2_2") (pintype "passive"))
      (node (ref "C0014") (pin "-") (pinfunction "-_-") (pintype "passive"))
      (node (ref "C0015") (pin "1") (pinfunction "1_1") (pintype "passive"))
      (node (ref "C0016") (pin "2") (pinfunction "2_2") (pintype "passive"))
      (node (ref "C0019") (pin "2") (pinfunction "2_2") (pintype "passive"))
      (node (ref "C0020") (pin "2") (pinfunction "2_2") (pintype "passive"))
      (node (ref "C0022") (pin "-") (pinfunction "-_-") (pintype "passive"))
      (node (ref "C0023") (pin "2") (pinfunction "2_2") (pintype "passive"))
      (node (ref "C0024") (pin "1") (pinfunction "1_1") (pintype "passive"))
      (node (ref "C0025") (pin "1") (pinfunction "1_1") (pintype "passive"))
      (node (ref "C0026") (pin "1") (pinfunction "1_1") (pintype "passive"))
      (node (ref "C0027") (pin "2") (pinfunction "2_2") (pintype "passive"))
      (node (ref "C0041") (pin "2") (pinfunction "2_2") (pintype "passive"))
      (node (ref "CIN1") (pin "-") (pinfunction "-_-") (pintype "passive"))
      (node (ref "COUT1") (pin "-") (pinfunction "-_-") (pintype "passive"))
      (node (ref "D1") (pin "A") (pinfunction "P$1_A") (pintype "bidirectional"))
      (node (ref "H_X") (pin "10") (pinfunction "SCK_10") (pintype "bidirectional"))
      (node (ref "H_X") (pin "6") (pinfunction "GND_6") (pintype "bidirectional"))
      (node (ref "H_X") (pin "8") (pinfunction "SI_8") (pintype "bidirectional"))
      (node (ref "H_X") (pin "9") (pinfunction "CSN_9") (pintype "bidirectional"))
      (node (ref "H_X") (pin "PAD") (pinfunction "GND_PAD") (pintype "bidirectional"))
      (node (ref "H_X") (pin "PAD2") (pinfunction "GND_PAD2") (pintype "bidirectional"))
      (node (ref "J1") (pin "1") (pinfunction "CENTER_PIN_1") (pintype "passive"))
      (node (ref "JP1") (pin "2") (pinfunction "2_2") (pintype "passive"))
      (node (ref "JP10") (pin "2") (pinfunction "2_2") (pintype "passive"))
      (node (ref "JP11") (pin "1") (pinfunction "1_1") (pintype "passive"))
      (node (ref "JP13") (pin "1") (pinfunction "1_1") (pintype "passive"))
      (node (ref "JP14") (pin "3") (pinfunction "3_3") (pintype "passive"))
      (node (ref "JP15") (pin "2") (pinfunction "2_2") (pintype "passive"))
      (node (ref "JP17") (pin "1") (pinfunction "1_1") (pintype "passive"))
      (node (ref "JP19") (pin "3") (pinfunction "3_3") (pintype "passive"))
      (node (ref "JP2") (pin "1") (pinfunction "1_1") (pintype "passive"))
      (node (ref "JP21") (pin "3") (pinfunction "3_3") (pintype "passive"))
      (node (ref "JP24") (pin "1") (pinfunction "1_1") (pintype "passive"))
      (node (ref "JP24") (pin "2") (pinfunction "2_2") (pintype "passive"))
      (node (ref "JP25") (pin "1") (pinfunction "1_1") (pintype "passive"))
      (node (ref "JP25") (pin "2") (pinfunction "2_2") (pintype "passive"))
      (node (ref "JP3") (pin "2") (pinfunction "2_2") (pintype "passive"))
      (node (ref "JP4") (pin "1") (pinfunction "1_1") (pintype "passive"))
      (node (ref "JP5") (pin "5") (pinfunction "5_5") (pintype "passive"))
      (node (ref "JP6") (pin "1") (pinfunction "1_1") (pintype "passive"))
      (node (ref "JP7") (pin "2") (pinfunction "2_2") (pintype "passive"))
      (node (ref "JP8") (pin "1") (pinfunction "1_1") (pintype "passive"))
      (node (ref "JP9") (pin "1") (pinfunction "1_1") (pintype "passive"))
      (node (ref "R0004") (pin "1") (pinfunction "1_1") (pintype "passive"))
      (node (ref "R0006") (pin "1") (pinfunction "1_1") (pintype "passive"))
      (node (ref "R0007") (pin "1") (pinfunction "1_1") (pintype "passive"))
      (node (ref "R0019") (pin "1") (pinfunction "1_1") (pintype "passive"))
      (node (ref "R0028") (pin "1") (pinfunction "1_1") (pintype "passive"))
      (node (ref "R0044") (pin "1") (pinfunction "1_1") (pintype "passive"))
      (node (ref "R0045") (pin "1") (pinfunction "A_1") (pintype "passive"))
      (node (ref "R0046") (pin "1") (pinfunction "A_1") (pintype "passive"))
      (node (ref "R0048") (pin "2") (pinfunction "2_2") (pintype "passive"))
      (node (ref "R0049") (pin "2") (pinfunction "2_2") (pintype "passive"))
      (node (ref "R0051") (pin "2") (pinfunction "2_2") (pintype "passive"))
      (node (ref "R0052") (pin "2") (pinfunction "2_2") (pintype "passive"))
      (node (ref "STM") (pin "L19") (pinfunction "GND1_L19") (pintype "bidirectional"))
      (node (ref "STM") (pin "L20") (pinfunction "GND2_L20") (pintype "bidirectional"))
      (node (ref "STM") (pin "L8") (pinfunction "GND0_L8") (pintype "bidirectional"))
      (node (ref "TEST_R3") (pin "2") (pinfunction "2_2") (pintype "passive"))
      (node (ref "U12") (pin "6") (pinfunction "GND_6") (pintype "passive"))
      (node (ref "U5") (pin "2") (pinfunction "COM_2") (pintype "bidirectional"))
      (node (ref "U5") (pin "TER") (pinfunction "COM_TER") (pintype "bidirectional"))
      (node (ref "X2") (pin "1") (pinfunction "KL_1") (pintype "passive"))
    )
    (net (code "17") (name "HEIZUNG") (class "Default")
      (node (ref "Q1") (pin "1") (pinfunction "G_1") (pintype "passive"))
      (node (ref "STM") (pin "R28") (pinfunction "PB14_R28") (pintype "bidirectional"))
    )
    (net (code "18") (name "LASER") (class "Default")
      (node (ref "R0042") (pin "1") (pinfunction "1_1") (pintype "passive"))
      (node (ref "STM") (pin "L28") (pinfunction "PA0_L28") (pintype "bidirectional"))
    )
    (net (code "19") (name "LED-GELB") (class "Default")
      (node (ref "R0024") (pin "2") (pinfunction "2_2") (pintype "passive"))
      (node (ref "STM") (pin "R15") (pinfunction "PA7_R15") (pintype "bidirectional"))
    )
    (net (code "20") (name "LED-GRüN") (class "Default")
      (node (ref "R0025") (pin "1") (pinfunction "1_1") (pintype "passive"))
      (node (ref "STM") (pin "R34") (pinfunction "PC4_R34") (pintype "bidirectional"))
    )
    (net (code "21") (name "LED-ROT") (class "Default")
      (node (ref "R0026") (pin "1") (pinfunction "1_1") (pintype "passive"))
      (node (ref "STM") (pin "R13") (pinfunction "PA6_R13") (pintype "bidirectional"))
    )
    (net (code "22") (name "LICHTSCHRANKE_LINKS_X") (class "Default")
      (node (ref "R0005") (pin "1") (pinfunction "1_1") (pintype "passive"))
      (node (ref "R0028") (pin "2") (pinfunction "2_2") (pintype "passive"))
      (node (ref "STM") (pin "R14") (pinfunction "PA11_R14") (pintype "bidirectional"))
    )
    (net (code "23") (name "LICHTSCHRANKE_RECHTS_X") (class "Default")
      (node (ref "R0002") (pin "1") (pinfunction "1_1") (pintype "passive"))
      (node (ref "R0004") (pin "2") (pinfunction "2_2") (pintype "passive"))
      (node (ref "STM") (pin "R12") (pinfunction "PA12_R12") (pintype "bidirectional"))
    )
    (net (code "24") (name "Net-(A4982_Y-CP1)") (class "Default")
      (node (ref "A4982_Y") (pin "1") (pinfunction "CP1_1") (pintype "bidirectional"))
      (node (ref "C0002") (pin "1") (pinfunction "1_1") (pintype "passive"))
    )
    (net (code "25") (name "Net-(A4982_Y-CP2)") (class "Default")
      (node (ref "A4982_Y") (pin "2") (pinfunction "CP2_2") (pintype "bidirectional"))
      (node (ref "C0002") (pin "2") (pinfunction "2_2") (pintype "passive"))
    )
    (net (code "26") (name "Net-(A4982_Y-DIR)") (class "Default")
      (node (ref "A4982_Y") (pin "14") (pinfunction "DIR_14") (pintype "bidirectional"))
      (node (ref "R0011") (pin "1") (pinfunction "1_1") (pintype "passive"))
    )
    (net (code "27") (name "Net-(A4982_Y-OUT1A)") (class "Default")
      (node (ref "A4982_Y") (pin "18") (pinfunction "OUT1A_18") (pintype "bidirectional"))
      (node (ref "X22") (pin "2") (pinfunction "KL_2") (pintype "passive"))
    )
    (net (code "28") (name "Net-(A4982_Y-OUT1B)") (class "Default")
      (node (ref "A4982_Y") (pin "15") (pinfunction "OUT1B_15") (pintype "bidirectional"))
      (node (ref "X22") (pin "1") (pinfunction "KL_1") (pintype "passive"))
    )
    (net (code "29") (name "Net-(A4982_Y-OUT2A)") (class "Default")
      (node (ref "A4982_Y") (pin "19") (pinfunction "OUT2A_19") (pintype "bidirectional"))
      (node (ref "X22") (pin "3") (pinfunction "KL_3") (pintype "passive"))
    )
    (net (code "30") (name "Net-(A4982_Y-OUT2B)") (class "Default")
      (node (ref "A4982_Y") (pin "22") (pinfunction "OUT2B_22") (pintype "bidirectional"))
      (node (ref "X22") (pin "4") (pinfunction "KL_4") (pintype "passive"))
    )
    (net (code "31") (name "Net-(A4982_Y-REF)") (class "Default")
      (node (ref "A4982_Y") (pin "12") (pinfunction "REF_12") (pintype "bidirectional"))
      (node (ref "C0010") (pin "1") (pinfunction "1_1") (pintype "passive"))
      (node (ref "R0023") (pin "2") (pinfunction "2_2") (pintype "passive"))
    )
    (net (code "32") (name "Net-(A4982_Y-ROSC)") (class "Default")
      (node (ref "A4982_Y") (pin "8") (pinfunction "ROSC_8") (pintype "bidirectional"))
      (node (ref "R0006") (pin "2") (pinfunction "2_2") (pintype "passive"))
    )
    (net (code "33") (name "Net-(A4982_Y-SENSE1)") (class "Default")
      (node (ref "A4982_Y") (pin "17") (pinfunction "SENSE1_17") (pintype "bidirectional"))
      (node (ref "R0049") (pin "1") (pinfunction "1_1") (pintype "passive"))
    )
    (net (code "34") (name "Net-(A4982_Y-SENSE2)") (class "Default")
      (node (ref "A4982_Y") (pin "20") (pinfunction "SENSE2_20") (pintype "bidirectional"))
      (node (ref "R0051") (pin "1") (pinfunction "1_1") (pintype "passive"))
    )
    (net (code "35") (name "Net-(A4982_Y-STEP)") (class "Default")
      (node (ref "A4982_Y") (pin "11") (pinfunction "STEP_11") (pintype "bidirectional"))
      (node (ref "R0010") (pin "2") (pinfunction "2_2") (pintype "passive"))
    )
    (net (code "36") (name "Net-(A4982_Y-VCP)") (class "Default")
      (node (ref "A4982_Y") (pin "3") (pinfunction "VCP_3") (pintype "bidirectional"))
      (node (ref "C0006") (pin "1") (pinfunction "1_1") (pintype "passive"))
    )
    (net (code "37") (name "Net-(A4982_Y-VREG)") (class "Default")
      (node (ref "A4982_Y") (pin "4") (pinfunction "VREG_4") (pintype "bidirectional"))
      (node (ref "C0004") (pin "1") (pinfunction "1_1") (pintype "passive"))
    )
    (net (code "38") (name "Net-(A4982_Y-_ENABLE)") (class "Default")
      (node (ref "A4982_Y") (pin "23") (pinfunction "_ENABLE_23") (pintype "bidirectional"))
      (node (ref "R0009") (pin "2") (pinfunction "2_2") (pintype "passive"))
    )
    (net (code "39") (name "Net-(A4982_Y1-CP1)") (class "Default")
      (node (ref "A4982_Y1") (pin "1") (pinfunction "CP1_1") (pintype "bidirectional"))
      (node (ref "C0018") (pin "1") (pinfunction "1_1") (pintype "passive"))
    )
    (net (code "40") (name "Net-(A4982_Y1-CP2)") (class "Default")
      (node (ref "A4982_Y1") (pin "2") (pinfunction "CP2_2") (pintype "bidirectional"))
      (node (ref "C0018") (pin "2") (pinfunction "2_2") (pintype "passive"))
    )
    (net (code "41") (name "Net-(A4982_Y1-DIR)") (class "Default")
      (node (ref "A4982_Y1") (pin "14") (pinfunction "DIR_14") (pintype "bidirectional"))
      (node (ref "R0036") (pin "1") (pinfunction "1_1") (pintype "passive"))
    )
    (net (code "42") (name "Net-(A4982_Y1-OUT1A)") (class "Default")
      (node (ref "A4982_Y1") (pin "18") (pinfunction "OUT1A_18") (pintype "bidirectional"))
      (node (ref "X1") (pin "2") (pinfunction "KL_2") (pintype "passive"))
    )
    (net (code "43") (name "Net-(A4982_Y1-OUT1B)") (class "Default")
      (node (ref "A4982_Y1") (pin "15") (pinfunction "OUT1B_15") (pintype "bidirectional"))
      (node (ref "X1") (pin "1") (pinfunction "KL_1") (pintype "passive"))
    )
    (net (code "44") (name "Net-(A4982_Y1-OUT2A)") (class "Default")
      (node (ref "A4982_Y1") (pin "19") (pinfunction "OUT2A_19") (pintype "bidirectional"))
      (node (ref "X1") (pin "3") (pinfunction "KL_3") (pintype "passive"))
    )
    (net (code "45") (name "Net-(A4982_Y1-OUT2B)") (class "Default")
      (node (ref "A4982_Y1") (pin "22") (pinfunction "OUT2B_22") (pintype "bidirectional"))
      (node (ref "X1") (pin "4") (pinfunction "KL_4") (pintype "passive"))
    )
    (net (code "46") (name "Net-(A4982_Y1-REF)") (class "Default")
      (node (ref "A4982_Y1") (pin "12") (pinfunction "REF_12") (pintype "bidirectional"))
      (node (ref "C0013") (pin "1") (pinfunction "1_1") (pintype "passive"))
      (node (ref "R0037") (pin "2") (pinfunction "2_2") (pintype "passive"))
    )
    (net (code "47") (name "Net-(A4982_Y1-ROSC)") (class "Default")
      (node (ref "A4982_Y1") (pin "8") (pinfunction "ROSC_8") (pintype "bidirectional"))
      (node (ref "R0019") (pin "2") (pinfunction "2_2") (pintype "passive"))
    )
    (net (code "48") (name "Net-(A4982_Y1-SENSE1)") (class "Default")
      (node (ref "A4982_Y1") (pin "17") (pinfunction "SENSE1_17") (pintype "bidirectional"))
      (node (ref "R0052") (pin "1") (pinfunction "1_1") (pintype "passive"))
    )
    (net (code "49") (name "Net-(A4982_Y1-SENSE2)") (class "Default")
      (node (ref "A4982_Y1") (pin "20") (pinfunction "SENSE2_20") (pintype "bidirectional"))
      (node (ref "R0048") (pin "1") (pinfunction "1_1") (pintype "passive"))
    )
    (net (code "50") (name "Net-(A4982_Y1-STEP)") (class "Default")
      (node (ref "A4982_Y1") (pin "11") (pinfunction "STEP_11") (pintype "bidirectional"))
      (node (ref "R0035") (pin "2") (pinfunction "2_2") (pintype "passive"))
    )
    (net (code "51") (name "Net-(A4982_Y1-VCP)") (class "Default")
      (node (ref "A4982_Y1") (pin "3") (pinfunction "VCP_3") (pintype "bidirectional"))
      (node (ref "C0021") (pin "1") (pinfunction "1_1") (pintype "passive"))
    )
    (net (code "52") (name "Net-(A4982_Y1-VREG)") (class "Default")
      (node (ref "A4982_Y1") (pin "4") (pinfunction "VREG_4") (pintype "bidirectional"))
      (node (ref "C0019") (pin "1") (pinfunction "1_1") (pintype "passive"))
    )
    (net (code "53") (name "Net-(A4982_Y1-_ENABLE)") (class "Default")
      (node (ref "A4982_Y1") (pin "23") (pinfunction "_ENABLE_23") (pintype "bidirectional"))
      (node (ref "R0034") (pin "2") (pinfunction "2_2") (pintype "passive"))
    )
    (net (code "54") (name "Net-(C0023-Pad1)") (class "Default")
      (node (ref "C0023") (pin "1") (pinfunction "1_1") (pintype "passive"))
      (node (ref "COUT1") (pin "+") (pinfunction "+_+") (pintype "passive"))
      (node (ref "L1") (pin "2") (pinfunction "2_2") (pintype "passive"))
      (node (ref "TEST_R") (pin "1") (pinfunction "1_1") (pintype "passive"))
      (node (ref "TEST_R2") (pin "2") (pinfunction "2_2") (pintype "passive"))
    )
    (net (code "55") (name "Net-(D1-P$2)") (class "Default")
      (node (ref "C0003") (pin "2") (pinfunction "2_2") (pintype "passive"))
      (node (ref "D1") (pin "C") (pinfunction "P$2_C") (pintype "bidirectional"))
      (node (ref "L1") (pin "1") (pinfunction "1_1") (pintype "passive"))
      (node (ref "U12") (pin "8") (pinfunction "VSW_8") (pintype "output"))
    )
    (net (code "56") (name "Net-(H_X-DIR)") (class "Default")
      (node (ref "H_X") (pin "1") (pinfunction "DIR_1") (pintype "bidirectional"))
      (node (ref "R0061") (pin "2") (pinfunction "2_2") (pintype "passive"))
    )
    (net (code "57") (name "Net-(H_X-DIS)") (class "Default")
      (node (ref "H_X") (pin "11") (pinfunction "DIS_11") (pintype "bidirectional"))
      (node (ref "R0063") (pin "2") (pinfunction "2_2") (pintype "passive"))
    )
    (net (code "58") (name "Net-(H_X-OUT1)") (class "Default")
      (node (ref "C0007") (pin "1") (pinfunction "1_1") (pintype "passive"))
      (node (ref "H_X") (pin "5") (pinfunction "OUT1_5") (pintype "bidirectional"))
      (node (ref "X27") (pin "2") (pinfunction "KL_2") (pintype "passive"))
    )
    (net (code "59") (name "Net-(H_X-OUT2)") (class "Default")
      (node (ref "C0008") (pin "1") (pinfunction "1_1") (pintype "passive"))
      (node (ref "H_X") (pin "7") (pinfunction "OUT2_7") (pintype "bidirectional"))
      (node (ref "X27") (pin "1") (pinfunction "KL_1") (pintype "passive"))
    )
    (net (code "60") (name "Net-(H_X-PWM)") (class "Default")
      (node (ref "H_X") (pin "12") (pinfunction "PWM_12") (pintype "bidirectional"))
      (node (ref "R0062") (pin "2") (pinfunction "2_2") (pintype "passive"))
    )
    (net (code "61") (name "Net-(H_X-SO)") (class "Default")
      (node (ref "H_X") (pin "3") (pinfunction "SO_3") (pintype "bidirectional"))
      (node (ref "R0001") (pin "2") (pinfunction "2_2") (pintype "passive"))
    )
    (net (code "62") (name "Net-(JP1-Pad1)") (class "Default")
      (node (ref "JP1") (pin "1") (pinfunction "1_1") (pintype "passive"))
      (node (ref "R0008") (pin "2") (pinfunction "2_2") (pintype "passive"))
      (node (ref "R0020") (pin "2") (pinfunction "2_2") (pintype "passive"))
    )
    (net (code "63") (name "Net-(JP2-Pad2)") (class "Default")
      (node (ref "JP2") (pin "2") (pinfunction "2_2") (pintype "passive"))
      (node (ref "R0024") (pin "1") (pinfunction "1_1") (pintype "passive"))
    )
    (net (code "64") (name "Net-(JP5-Pad1)") (class "Default")
      (node (ref "JP5") (pin "1") (pinfunction "1_1") (pintype "passive"))
      (node (ref "R0030") (pin "1") (pinfunction "1_1") (pintype "passive"))
    )
    (net (code "65") (name "Net-(JP6-Pad2)") (class "Default")
      (node (ref "JP6") (pin "2") (pinfunction "2_2") (pintype "passive"))
      (node (ref "R0025") (pin "2") (pinfunction "2_2") (pintype "passive"))
    )
    (net (code "66") (name "Net-(JP8-Pad2)") (class "Default")
      (node (ref "JP8") (pin "2") (pinfunction "2_2") (pintype "passive"))
      (node (ref "R0053") (pin "1") (pinfunction "1_1") (pintype "passive"))
    )
    (net (code "67") (name "Net-(JP9-Pad2)") (class "Default")
      (node (ref "JP9") (pin "2") (pinfunction "2_2") (pintype "passive"))
      (node (ref "R0031") (pin "1") (pinfunction "1_1") (pintype "passive"))
    )
    (net (code "68") (name "Net-(JP10-Pad3)") (class "Default")
      (node (ref "JP10") (pin "3") (pinfunction "3_3") (pintype "passive"))
      (node (ref "R0033") (pin "2") (pinfunction "2_2") (pintype "passive"))
    )
    (net (code "69") (name "Net-(JP13-Pad2)") (class "Default")
      (node (ref "JP13") (pin "2") (pinfunction "2_2") (pintype "passive"))
      (node (ref "R0026") (pin "2") (pinfunction "2_2") (pintype "passive"))
    )
    (net (code "70") (name "Net-(JP14-Pad2)") (class "Default")
      (node (ref "JP14") (pin "2") (pinfunction "2_2") (pintype "passive"))
      (node (ref "R0042") (pin "2") (pinfunction "2_2") (pintype "passive"))
    )
    (net (code "71") (name "Net-(JP17-Pad3)") (class "Default")
      (node (ref "JP17") (pin "3") (pinfunction "3_3") (pintype "passive"))
      (node (ref "R0015") (pin "2") (pinfunction "2_2") (pintype "passive"))
    )
    (net (code "72") (name "Net-(JP19-Pad2)") (class "Default")
      (node (ref "JP19") (pin "2") (pinfunction "2_2") (pintype "passive"))
      (node (ref "R0003") (pin "2") (pinfunction "2_2") (pintype "passive"))
    )
    (net (code "73") (name "Net-(JP21-Pad2)") (class "Default")
      (node (ref "JP21") (pin "2") (pinfunction "2_2") (pintype "passive"))
      (node (ref "R0018") (pin "2") (pinfunction "2_2") (pintype "passive"))
    )
    (net (code "74") (name "Net-(JP23-Pad1)") (class "Default")
      (node (ref "JP23") (pin "1") (pinfunction "1_1") (pintype "passive"))
      (node (ref "R0016") (pin "1") (pinfunction "1_1") (pintype "passive"))
      (node (ref "R0043") (pin "2") (pinfunction "2_2") (pintype "passive"))
    )
    (net (code "75") (name "Net-(JP24-Pad3)") (class "Default")
      (node (ref "JP24") (pin "3") (pinfunction "3_3") (pintype "passive"))
      (node (ref "R0002") (pin "2") (pinfunction "2_2") (pintype "passive"))
    )
    (net (code "76") (name "Net-(JP24-Pad5)") (class "Default")
      (node (ref "JP24") (pin "5") (pinfunction "5_5") (pintype "passive"))
      (node (ref "R0029") (pin "1") (pinfunction "1_1") (pintype "passive"))
    )
    (net (code "77") (name "Net-(JP25-Pad3)") (class "Default")
      (node (ref "JP25") (pin "3") (pinfunction "3_3") (pintype "passive"))
      (node (ref "R0005") (pin "2") (pinfunction "2_2") (pintype "passive"))
    )
    (net (code "78") (name "Net-(JP25-Pad5)") (class "Default")
      (node (ref "JP25") (pin "5") (pinfunction "5_5") (pintype "passive"))
      (node (ref "R0032") (pin "1") (pinfunction "1_1") (pintype "passive"))
    )
    (net (code "79") (name "Net-(Q1-S)") (class "Default")
      (node (ref "JP11") (pin "2") (pinfunction "2_2") (pintype "passive"))
      (node (ref "Q1") (pin "2") (pinfunction "S_2") (pintype "passive"))
    )
    (net (code "80") (name "Net-(R0017-Pad1)") (class "Default")
      (node (ref "R0017") (pin "1") (pinfunction "1_1") (pintype "passive"))
      (node (ref "R0043") (pin "1") (pinfunction "1_1") (pintype "passive"))
      (node (ref "R0044") (pin "2") (pinfunction "2_2") (pintype "passive"))
    )
    (net (code "81") (name "Net-(R0045-S)") (class "Default")
      (node (ref "R0037") (pin "1") (pinfunction "1_1") (pintype "passive"))
      (node (ref "R0045") (pin "2") (pinfunction "S_2") (pintype "passive"))
    )
    (net (code "82") (name "Net-(R0046-S)") (class "Default")
      (node (ref "R0023") (pin "1") (pinfunction "1_1") (pintype "passive"))
      (node (ref "R0046") (pin "2") (pinfunction "S_2") (pintype "passive"))
    )
    (net (code "83") (name "Net-(STM-E5V)") (class "Default")
      (node (ref "R0027") (pin "2") (pinfunction "2_2") (pintype "passive"))
      (node (ref "STM") (pin "L6") (pinfunction "E5V_L6") (pintype "bidirectional"))
    )
    (net (code "84") (name "Net-(STM-VDD)") (class "Default")
      (node (ref "JP12") (pin "2") (pinfunction "2_2") (pintype "passive"))
      (node (ref "STM") (pin "L5") (pinfunction "VDD_L5") (pintype "bidirectional"))
    )
    (net (code "85") (name "Net-(STM-VIN)") (class "Default")
      (node (ref "JP12") (pin "1") (pinfunction "1_1") (pintype "passive"))
      (node (ref "STM") (pin "L24") (pinfunction "VIN_L24") (pintype "bidirectional"))
    )
    (net (code "86") (name "Net-(U12-CB)") (class "Default")
      (node (ref "C0003") (pin "1") (pinfunction "1_1") (pintype "passive"))
      (node (ref "U12") (pin "1") (pinfunction "CB_1") (pintype "input"))
    )
    (net (code "87") (name "N§VV") (class "Default")
      (node (ref "JP24") (pin "4") (pinfunction "4_4") (pintype "passive"))
      (node (ref "JP25") (pin "4") (pinfunction "4_4") (pintype "passive"))
      (node (ref "TEST_R2") (pin "1") (pinfunction "1_1") (pintype "passive"))
      (node (ref "TEST_R3") (pin "1") (pinfunction "1_1") (pintype "passive"))
      (node (ref "U12") (pin "4") (pinfunction "FB_4") (pintype "input"))
    )
    (net (code "88") (name "PWM-H") (class "Default")
      (node (ref "R0062") (pin "1") (pinfunction "1_1") (pintype "passive"))
      (node (ref "STM") (pin "L38") (pinfunction "PC0_L38") (pintype "bidirectional"))
    )
    (net (code "89") (name "RESET1_Z") (class "Default")
      (node (ref "A4982_Y1") (pin "7") (pinfunction "_RST_7") (pintype "bidirectional"))
      (node (ref "R0038") (pin "2") (pinfunction "2_2") (pintype "passive"))
      (node (ref "STM") (pin "R1") (pinfunction "PC9_R1") (pintype "bidirectional"))
    )
    (net (code "90") (name "RESET2_Y") (class "Default")
      (node (ref "A4982_Y") (pin "7") (pinfunction "_RST_7") (pintype "bidirectional"))
      (node (ref "R0021") (pin "2") (pinfunction "2_2") (pintype "passive"))
      (node (ref "STM") (pin "L21") (pinfunction "PB7_L21") (pintype "bidirectional"))
    )
    (net (code "91") (name "SCL") (class "Default")
      (node (ref "JP5") (pin "3") (pinfunction "3_3") (pintype "passive"))
      (node (ref "STM") (pin "R3") (pinfunction "PB8_R3") (pintype "bidirectional"))
    )
    (net (code "92") (name "SDA") (class "Default")
      (node (ref "JP5") (pin "2") (pinfunction "2_2") (pintype "passive"))
      (node (ref "STM") (pin "R5") (pinfunction "PB9_R5") (pintype "bidirectional"))
    )
    (net (code "93") (name "SLEEP1_Z") (class "Default")
      (node (ref "A4982_Y1") (pin "9") (pinfunction "_SLEEP_9") (pintype "bidirectional"))
      (node (ref "R0039") (pin "2") (pinfunction "2_2") (pintype "passive"))
      (node (ref "STM") (pin "R23") (pinfunction "PA8_R23") (pintype "bidirectional"))
    )
    (net (code "94") (name "SLEEP2_Y") (class "Default")
      (node (ref "A4982_Y") (pin "9") (pinfunction "_SLEEP_9") (pintype "bidirectional"))
      (node (ref "R0022") (pin "2") (pinfunction "2_2") (pintype "passive"))
      (node (ref "STM") (pin "L4") (pinfunction "PD2_L4") (pintype "bidirectional"))
    )
    (net (code "95") (name "SO") (class "Default")
      (node (ref "R0001") (pin "1") (pinfunction "1_1") (pintype "passive"))
      (node (ref "STM") (pin "L37") (pinfunction "PC3_L37") (pintype "bidirectional"))
    )
    (net (code "96") (name "STEP1_Z") (class "Default")
      (node (ref "R0035") (pin "1") (pinfunction "1_1") (pintype "passive"))
      (node (ref "STM") (pin "R4") (pinfunction "PC6_R4") (pintype "bidirectional"))
    )
    (net (code "97") (name "STEP2_Y") (class "Default")
      (node (ref "R0010") (pin "1") (pinfunction "1_1") (pintype "passive"))
      (node (ref "STM") (pin "R27") (pinfunction "PB4_R27") (pintype "bidirectional"))
    )
    (net (code "98") (name "TASTER1_START") (class "Default")
      (node (ref "JP7") (pin "1") (pinfunction "1_1") (pintype "passive"))
      (node (ref "R0012") (pin "2") (pinfunction "2_2") (pintype "passive"))
      (node (ref "STM") (pin "R16") (pinfunction "PB12_R16") (pintype "bidirectional"))
    )
    (net (code "99") (name "TASTER2_STOP") (class "Default")
      (node (ref "JP3") (pin "1") (pinfunction "1_1") (pintype "passive"))
      (node (ref "R0013") (pin "2") (pinfunction "2_2") (pintype "passive"))
      (node (ref "STM") (pin "R30") (pinfunction "PB13_R30") (pintype "bidirectional"))
    )
    (net (code "100") (name "TASTER3_PAUSE") (class "Default")
      (node (ref "JP4") (pin "2") (pinfunction "2_2") (pintype "passive"))
      (node (ref "R0014") (pin "2") (pinfunction "2_2") (pintype "passive"))
      (node (ref "STM") (pin "R25") (pinfunction "PB10_R25") (pintype "bidirectional"))
    )
    (net (code "101") (name "TEMP-µ") (class "Default")
      (node (ref "C0011") (pin "1") (pinfunction "1_1") (pintype "passive"))
      (node (ref "R0020") (pin "1") (pinfunction "1_1") (pintype "passive"))
      (node (ref "STM") (pin "R26") (pinfunction "PB15_R26") (pintype "bidirectional"))
    )
    (net (code "102") (name "TEST-I-REGLER") (class "Default")
      (node (ref "C0025") (pin "2") (pinfunction "2_2") (pintype "passive"))
      (node (ref "R0053") (pin "2") (pinfunction "2_2") (pintype "passive"))
      (node (ref "STM") (pin "L30") (pinfunction "PA1_L30") (pintype "bidirectional"))
    )
    (net (code "103") (name "TEST-P-REGLER") (class "Default")
      (node (ref "C0024") (pin "2") (pinfunction "2_2") (pintype "passive"))
      (node (ref "R0031") (pin "2") (pinfunction "2_2") (pintype "passive"))
      (node (ref "STM") (pin "L32") (pinfunction "PA4_L32") (pintype "bidirectional"))
    )
    (net (code "104") (name "TüR_SCHALTER") (class "Default")
      (node (ref "JP21") (pin "1") (pinfunction "1_1") (pintype "passive"))
      (node (ref "R0017") (pin "2") (pinfunction "2_2") (pintype "passive"))
      (node (ref "STM") (pin "R18") (pinfunction "PB11_R18") (pintype "bidirectional"))
    )
    (net (code "105") (name "unconnected-(A4982_Y-MS1-Pad5)") (class "Default")
      (node (ref "A4982_Y") (pin "5") (pinfunction "MS1_5") (pintype "bidirectional"))
    )
    (net (code "106") (name "unconnected-(A4982_Y-MS2-Pad6)") (class "Default")
      (node (ref "A4982_Y") (pin "6") (pinfunction "MS2_6") (pintype "bidirectional"))
    )
    (net (code "107") (name "unconnected-(A4982_Y1-MS1-Pad5)") (class "Default")
      (node (ref "A4982_Y1") (pin "5") (pinfunction "MS1_5") (pintype "bidirectional"))
    )
    (net (code "108") (name "unconnected-(A4982_Y1-MS2-Pad6)") (class "Default")
      (node (ref "A4982_Y1") (pin "6") (pinfunction "MS2_6") (pintype "bidirectional"))
    )
    (net (code "109") (name "unconnected-(STM-+3V3-PadL16)") (class "Default")
      (node (ref "STM") (pin "L16") (pinfunction "+3V3_L16") (pintype "bidirectional"))
    )
    (net (code "110") (name "unconnected-(STM-+5V-PadL18)") (class "Default")
      (node (ref "STM") (pin "L18") (pinfunction "+5V_L18") (pintype "bidirectional"))
    )
    (net (code "111") (name "unconnected-(STM-AGND-PadR32)") (class "Default")
      (node (ref "STM") (pin "R32") (pinfunction "AGND_R32") (pintype "bidirectional"))
    )
    (net (code "112") (name "unconnected-(STM-AVDD-PadR7)") (class "Default")
      (node (ref "STM") (pin "R7") (pinfunction "AVDD_R7") (pintype "bidirectional"))
    )
    (net (code "113") (name "unconnected-(STM-BOOT0-PadL7)") (class "Default")
      (node (ref "STM") (pin "L7") (pinfunction "BOOT0_L7") (pintype "bidirectional"))
    )
    (net (code "114") (name "unconnected-(STM-GND3-PadL22)") (class "Default")
      (node (ref "STM") (pin "L22") (pinfunction "GND3_L22") (pintype "bidirectional"))
    )
    (net (code "115") (name "unconnected-(STM-GND4-PadR9)") (class "Default")
      (node (ref "STM") (pin "R9") (pinfunction "GND4_R9") (pintype "bidirectional"))
    )
    (net (code "116") (name "unconnected-(STM-GND5-PadR20)") (class "Default")
      (node (ref "STM") (pin "R20") (pinfunction "GND5_R20") (pintype "bidirectional"))
    )
    (net (code "117") (name "unconnected-(STM-IOREF-PadL12)") (class "Default")
      (node (ref "STM") (pin "L12") (pinfunction "IOREF_L12") (pintype "bidirectional"))
    )
    (net (code "118") (name "unconnected-(STM-NC0-PadL9)") (class "Default")
      (node (ref "STM") (pin "L9") (pinfunction "NC0_L9") (pintype "bidirectional"))
    )
    (net (code "119") (name "unconnected-(STM-NC1-PadL10)") (class "Default")
      (node (ref "STM") (pin "L10") (pinfunction "NC1_L10") (pintype "bidirectional"))
    )
    (net (code "120") (name "unconnected-(STM-NC2-PadL11)") (class "Default")
      (node (ref "STM") (pin "L11") (pinfunction "NC2_L11") (pintype "bidirectional"))
    )
    (net (code "121") (name "unconnected-(STM-NC3-PadL26)") (class "Default")
      (node (ref "STM") (pin "L26") (pinfunction "NC3_L26") (pintype "bidirectional"))
    )
    (net (code "122") (name "unconnected-(STM-NC4-PadR10)") (class "Default")
      (node (ref "STM") (pin "R10") (pinfunction "NC4_R10") (pintype "bidirectional"))
    )
    (net (code "123") (name "unconnected-(STM-NC5-PadR36)") (class "Default")
      (node (ref "STM") (pin "R36") (pinfunction "NC5_R36") (pintype "bidirectional"))
    )
    (net (code "124") (name "unconnected-(STM-NC6-PadR38)") (class "Default")
      (node (ref "STM") (pin "R38") (pinfunction "NC6_R38") (pintype "bidirectional"))
    )
    (net (code "125") (name "unconnected-(STM-PA2-PadR35)") (class "Default")
      (node (ref "STM") (pin "R35") (pinfunction "PA2_R35") (pintype "bidirectional"))
    )
    (net (code "126") (name "unconnected-(STM-PA3-PadR37)") (class "Default")
      (node (ref "STM") (pin "R37") (pinfunction "PA3_R37") (pintype "bidirectional"))
    )
    (net (code "127") (name "unconnected-(STM-PA5-PadR11)") (class "Default")
      (node (ref "STM") (pin "R11") (pinfunction "PA5_R11") (pintype "bidirectional"))
    )
    (net (code "128") (name "unconnected-(STM-PA9-PadR21)") (class "Default")
      (node (ref "STM") (pin "R21") (pinfunction "PA9_R21") (pintype "bidirectional"))
    )
    (net (code "129") (name "unconnected-(STM-PA10-PadR33)") (class "Default")
      (node (ref "STM") (pin "R33") (pinfunction "PA10_R33") (pintype "bidirectional"))
    )
    (net (code "130") (name "unconnected-(STM-PA13-PadL13)") (class "Default")
      (node (ref "STM") (pin "L13") (pinfunction "PA13_L13") (pintype "bidirectional"))
    )
    (net (code "131") (name "unconnected-(STM-PA14-PadL15)") (class "Default")
      (node (ref "STM") (pin "L15") (pinfunction "PA14_L15") (pintype "bidirectional"))
    )
    (net (code "132") (name "unconnected-(STM-PA15-PadL17)") (class "Default")
      (node (ref "STM") (pin "L17") (pinfunction "PA15_L17") (pintype "bidirectional"))
    )
    (net (code "133") (name "unconnected-(STM-PB1-PadR24)") (class "Default")
      (node (ref "STM") (pin "R24") (pinfunction "PB1_R24") (pintype "bidirectional"))
    )
    (net (code "134") (name "unconnected-(STM-PB3-PadR31)") (class "Default")
      (node (ref "STM") (pin "R31") (pinfunction "PB3_R31") (pintype "bidirectional"))
    )
    (net (code "135") (name "unconnected-(STM-PC11-PadL2)") (class "Default")
      (node (ref "STM") (pin "L2") (pinfunction "PC11_L2") (pintype "bidirectional"))
    )
    (net (code "136") (name "unconnected-(STM-PC12-PadL3)") (class "Default")
      (node (ref "STM") (pin "L3") (pinfunction "PC12_L3") (pintype "bidirectional"))
    )
    (net (code "137") (name "unconnected-(STM-PC13-PadL23)") (class "Default")
      (node (ref "STM") (pin "L23") (pinfunction "PC13_L23") (pintype "bidirectional"))
    )
    (net (code "138") (name "unconnected-(STM-PC14-PadL25)") (class "Default")
      (node (ref "STM") (pin "L25") (pinfunction "PC14_L25") (pintype "bidirectional"))
    )
    (net (code "139") (name "unconnected-(STM-PC15-PadL27)") (class "Default")
      (node (ref "STM") (pin "L27") (pinfunction "PC15_L27") (pintype "bidirectional"))
    )
    (net (code "140") (name "unconnected-(STM-PF0-PadL29)") (class "Default")
      (node (ref "STM") (pin "L29") (pinfunction "PF0_L29") (pintype "bidirectional"))
    )
    (net (code "141") (name "unconnected-(STM-PF1-PadL31)") (class "Default")
      (node (ref "STM") (pin "L31") (pinfunction "PF1_L31") (pintype "bidirectional"))
    )
    (net (code "142") (name "unconnected-(STM-RESET-PadL14)") (class "Default")
      (node (ref "STM") (pin "L14") (pinfunction "RESET_L14") (pintype "bidirectional"))
    )
    (net (code "143") (name "unconnected-(STM-U5V-PadR8)") (class "Default")
      (node (ref "STM") (pin "R8") (pinfunction "U5V_R8") (pintype "bidirectional"))
    )
    (net (code "144") (name "unconnected-(STM-VBAT-PadL33)") (class "Default")
      (node (ref "STM") (pin "L33") (pinfunction "VBAT_L33") (pintype "bidirectional"))
    )
    (net (code "145") (name "unconnected-(U12-ON{slash}~{OFF}-Pad5)") (class "Default")
      (node (ref "U12") (pin "5") (pinfunction "ON/~{OFF}_5") (pintype "input"))
    )
    (net (code "146") (name "unconnected-(U12-SS-Pad2)") (class "Default")
      (node (ref "U12") (pin "2") (pinfunction "SS_2") (pintype "input"))
    )
    (net (code "147") (name "unconnected-(U12-SYNC-Pad3)") (class "Default")
      (node (ref "U12") (pin "3") (pinfunction "SYNC_3") (pintype "input"))
    )
  )
)
